# transponder-11_8_0.net
KiCad netlist of a schematic drawn in EAGLE
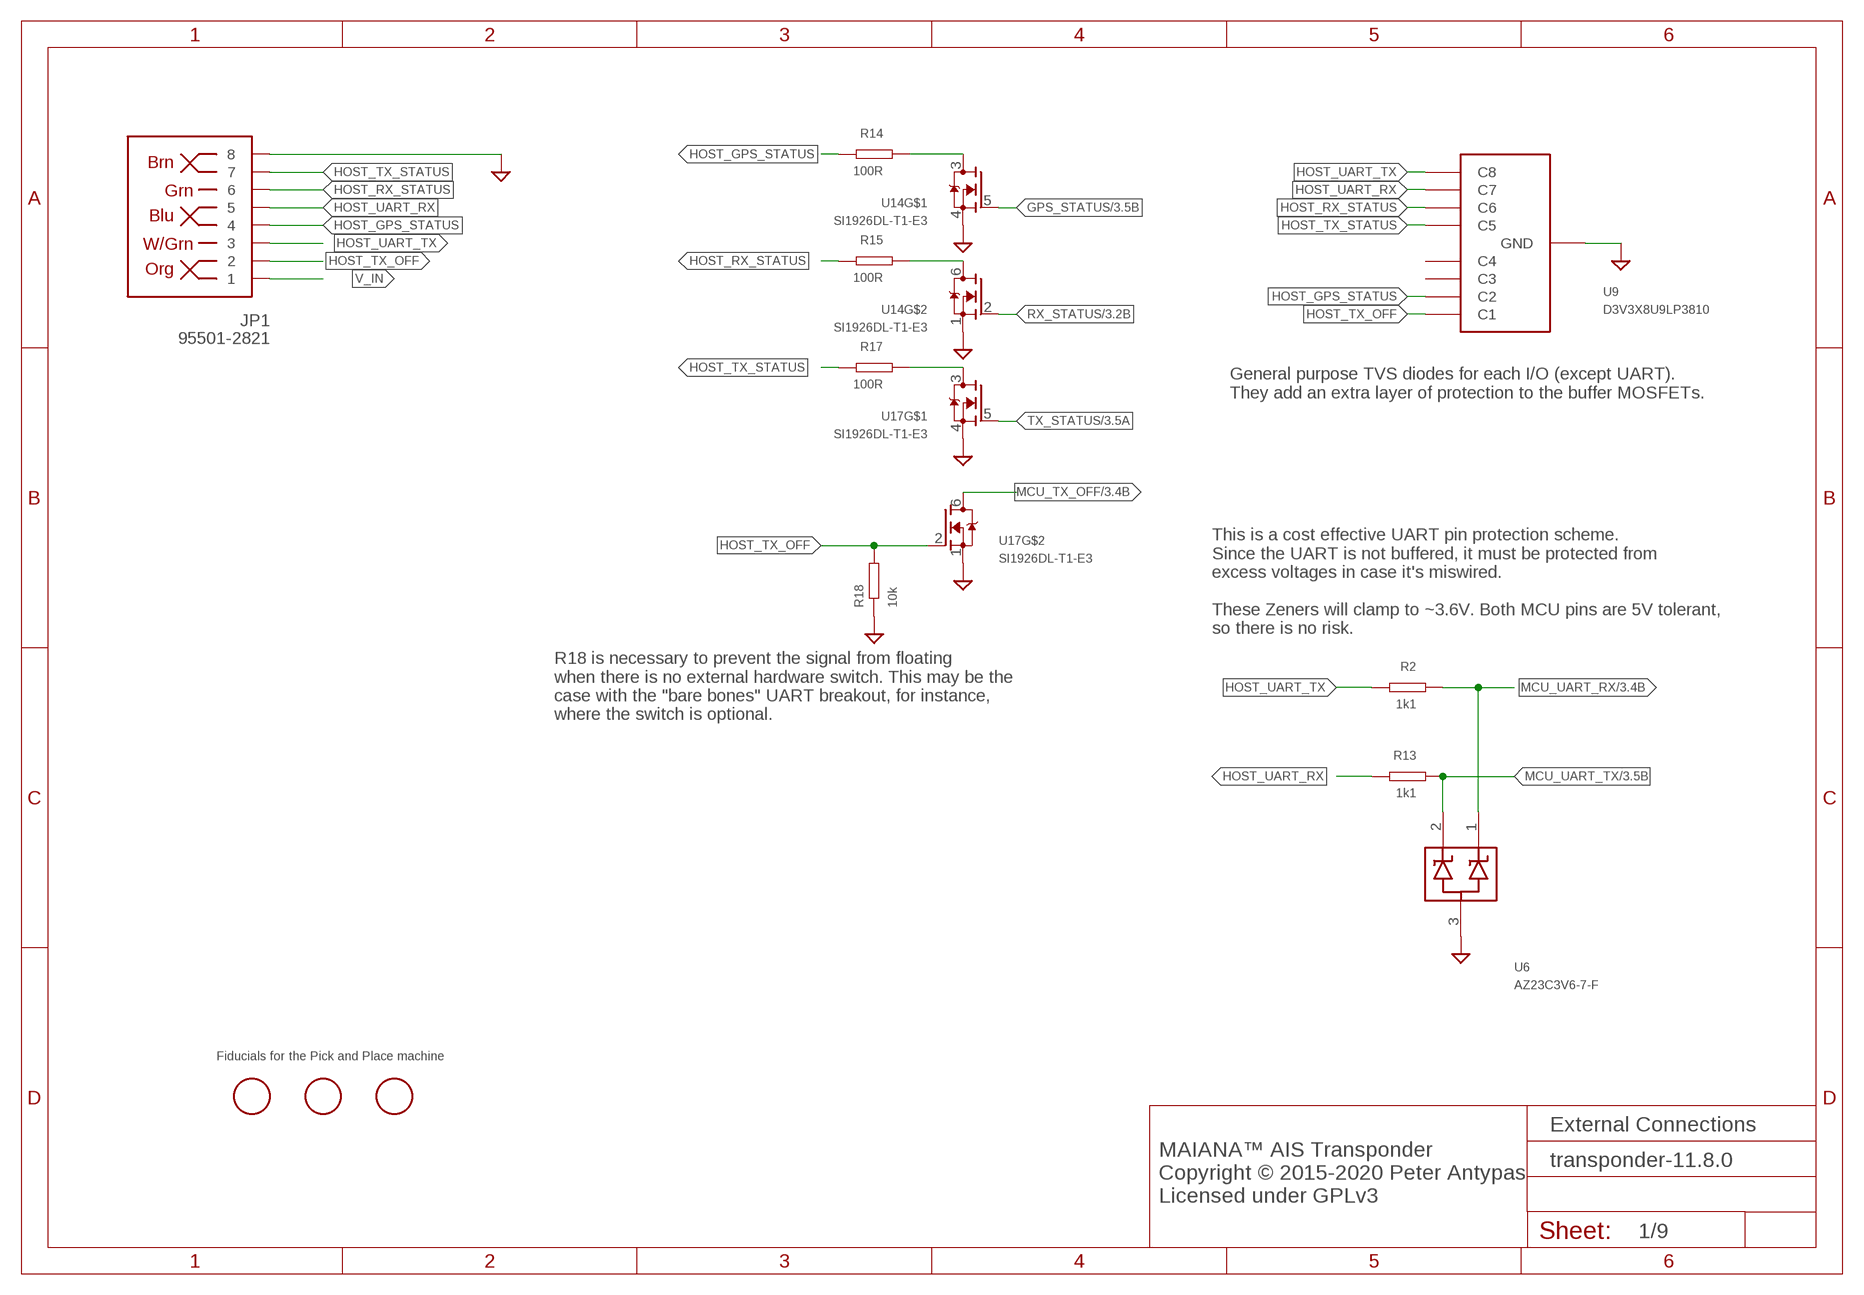
[diagram p0: schematic, sheet 1]
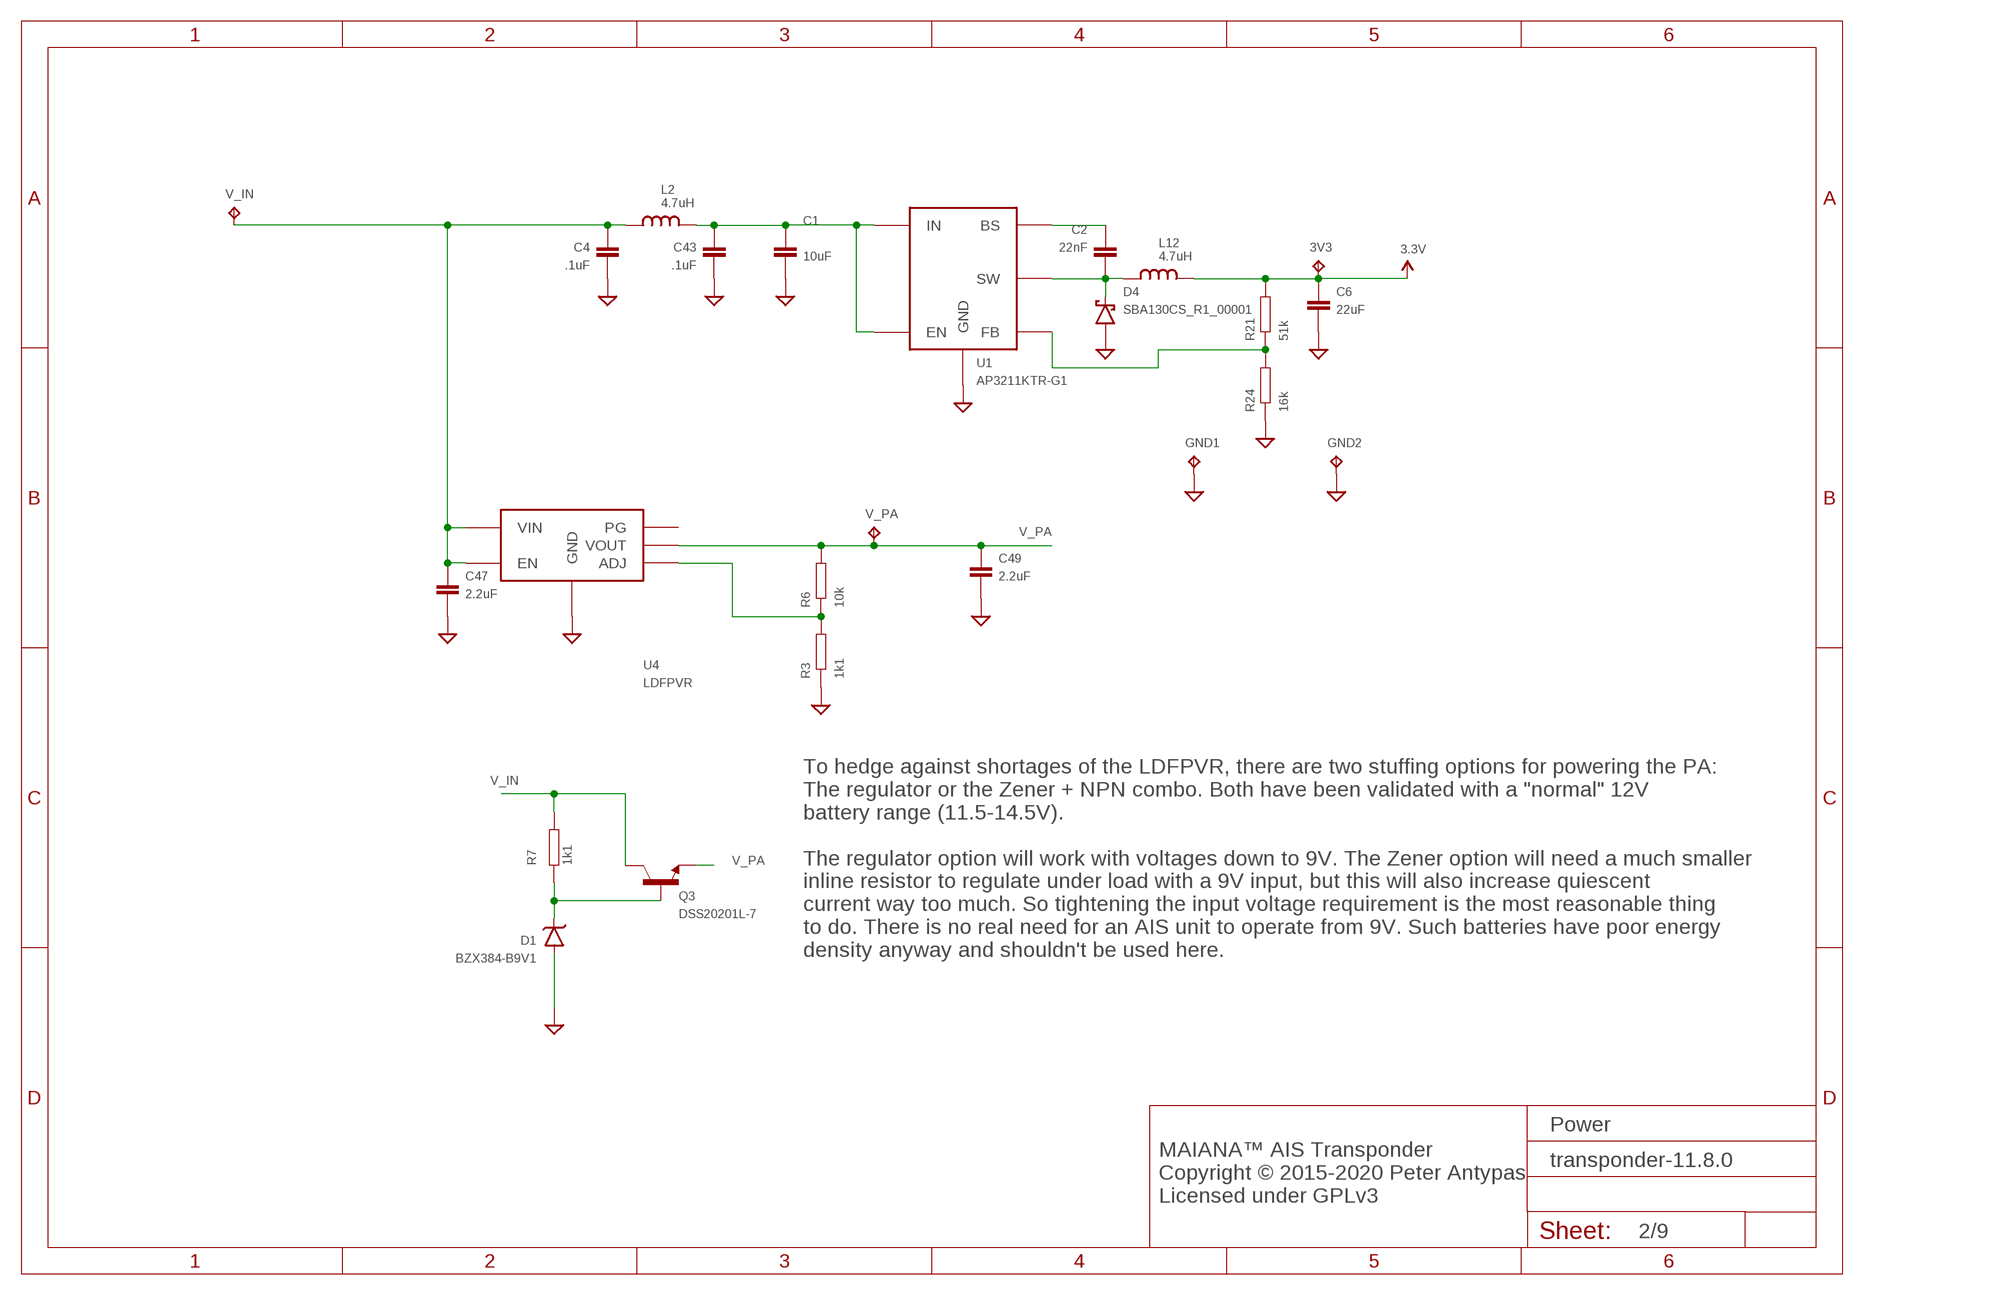
[diagram p1: schematic, sheet 2]
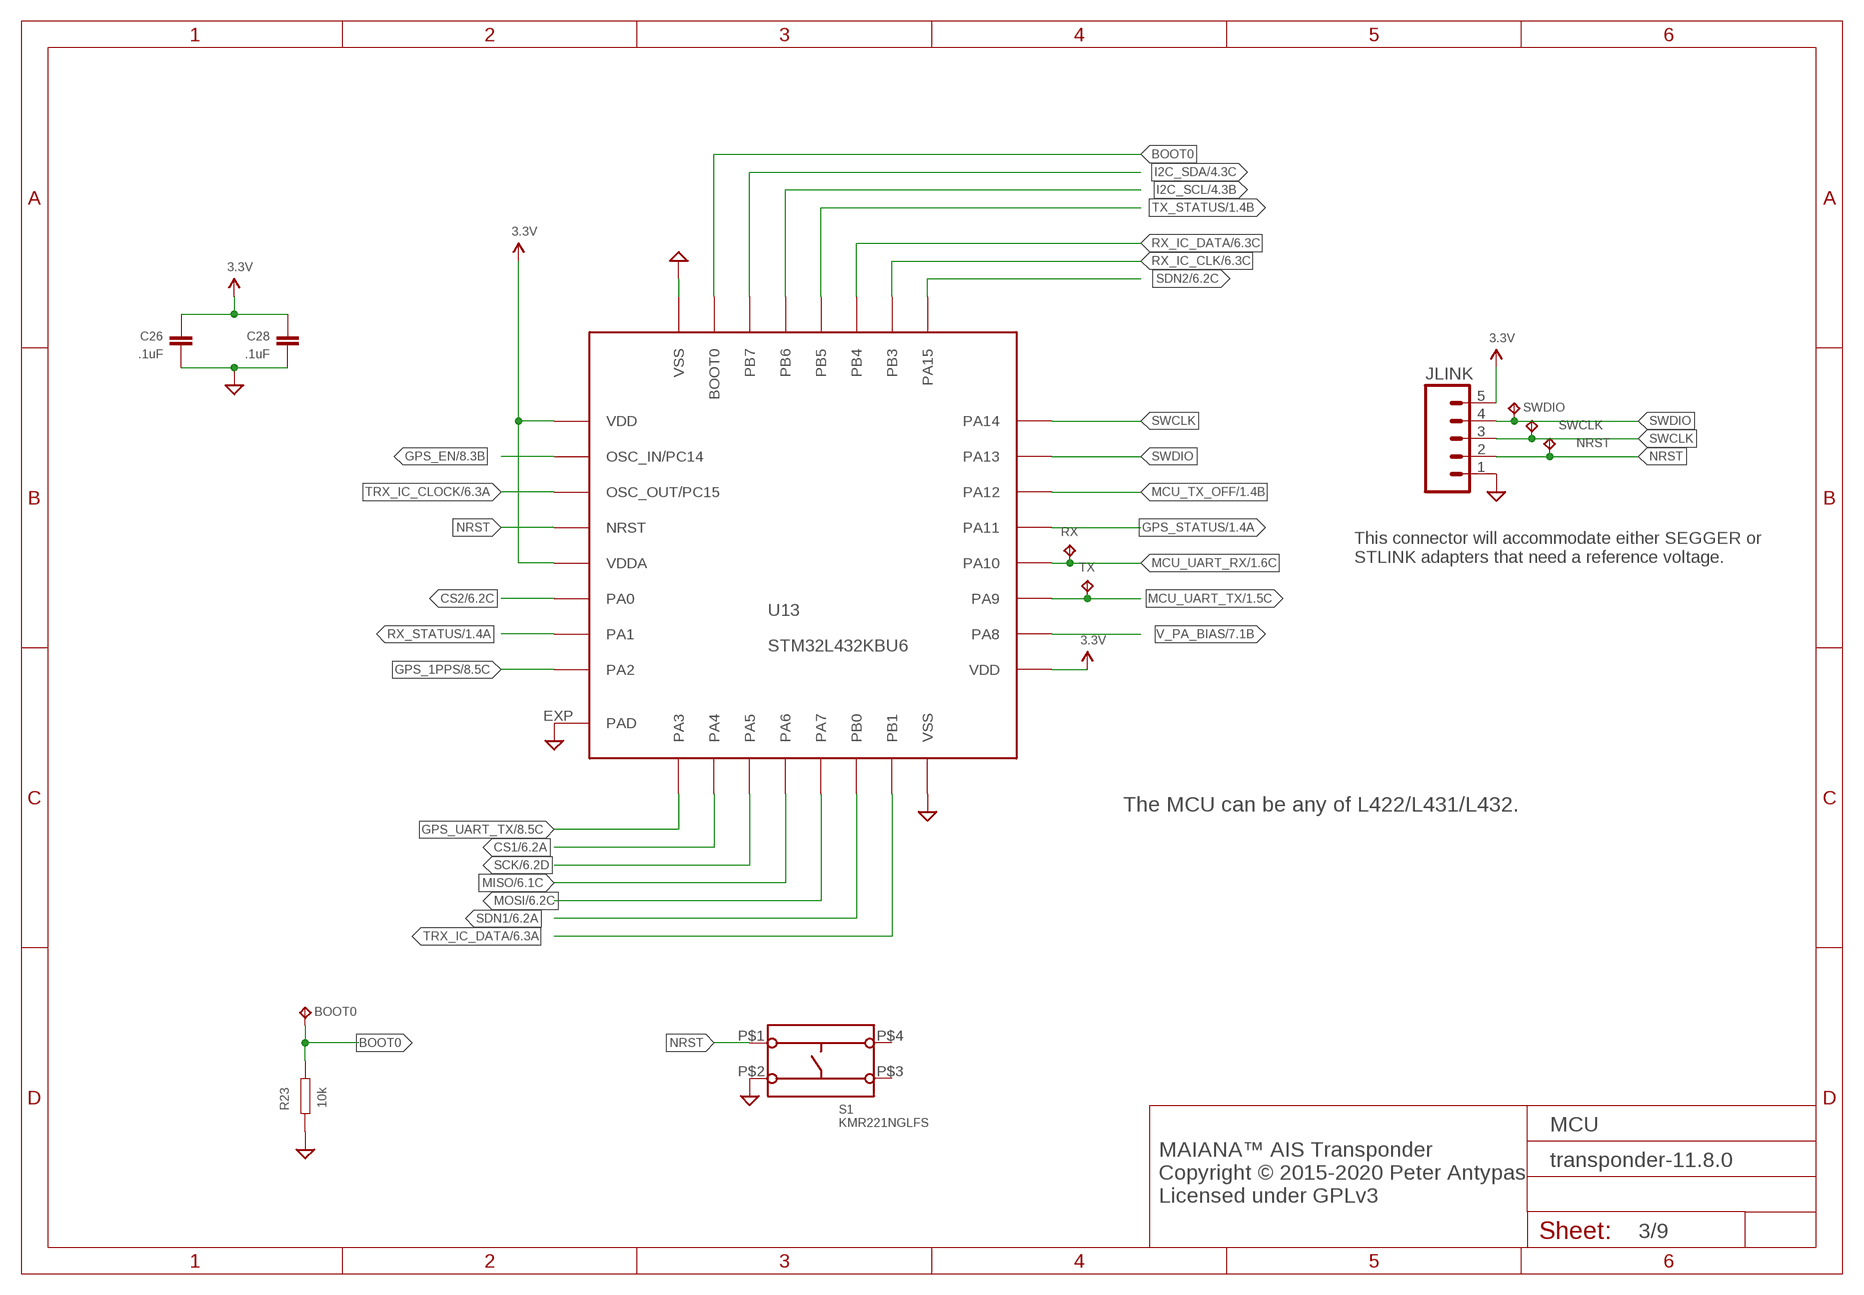
[diagram p2: schematic, sheet 3]
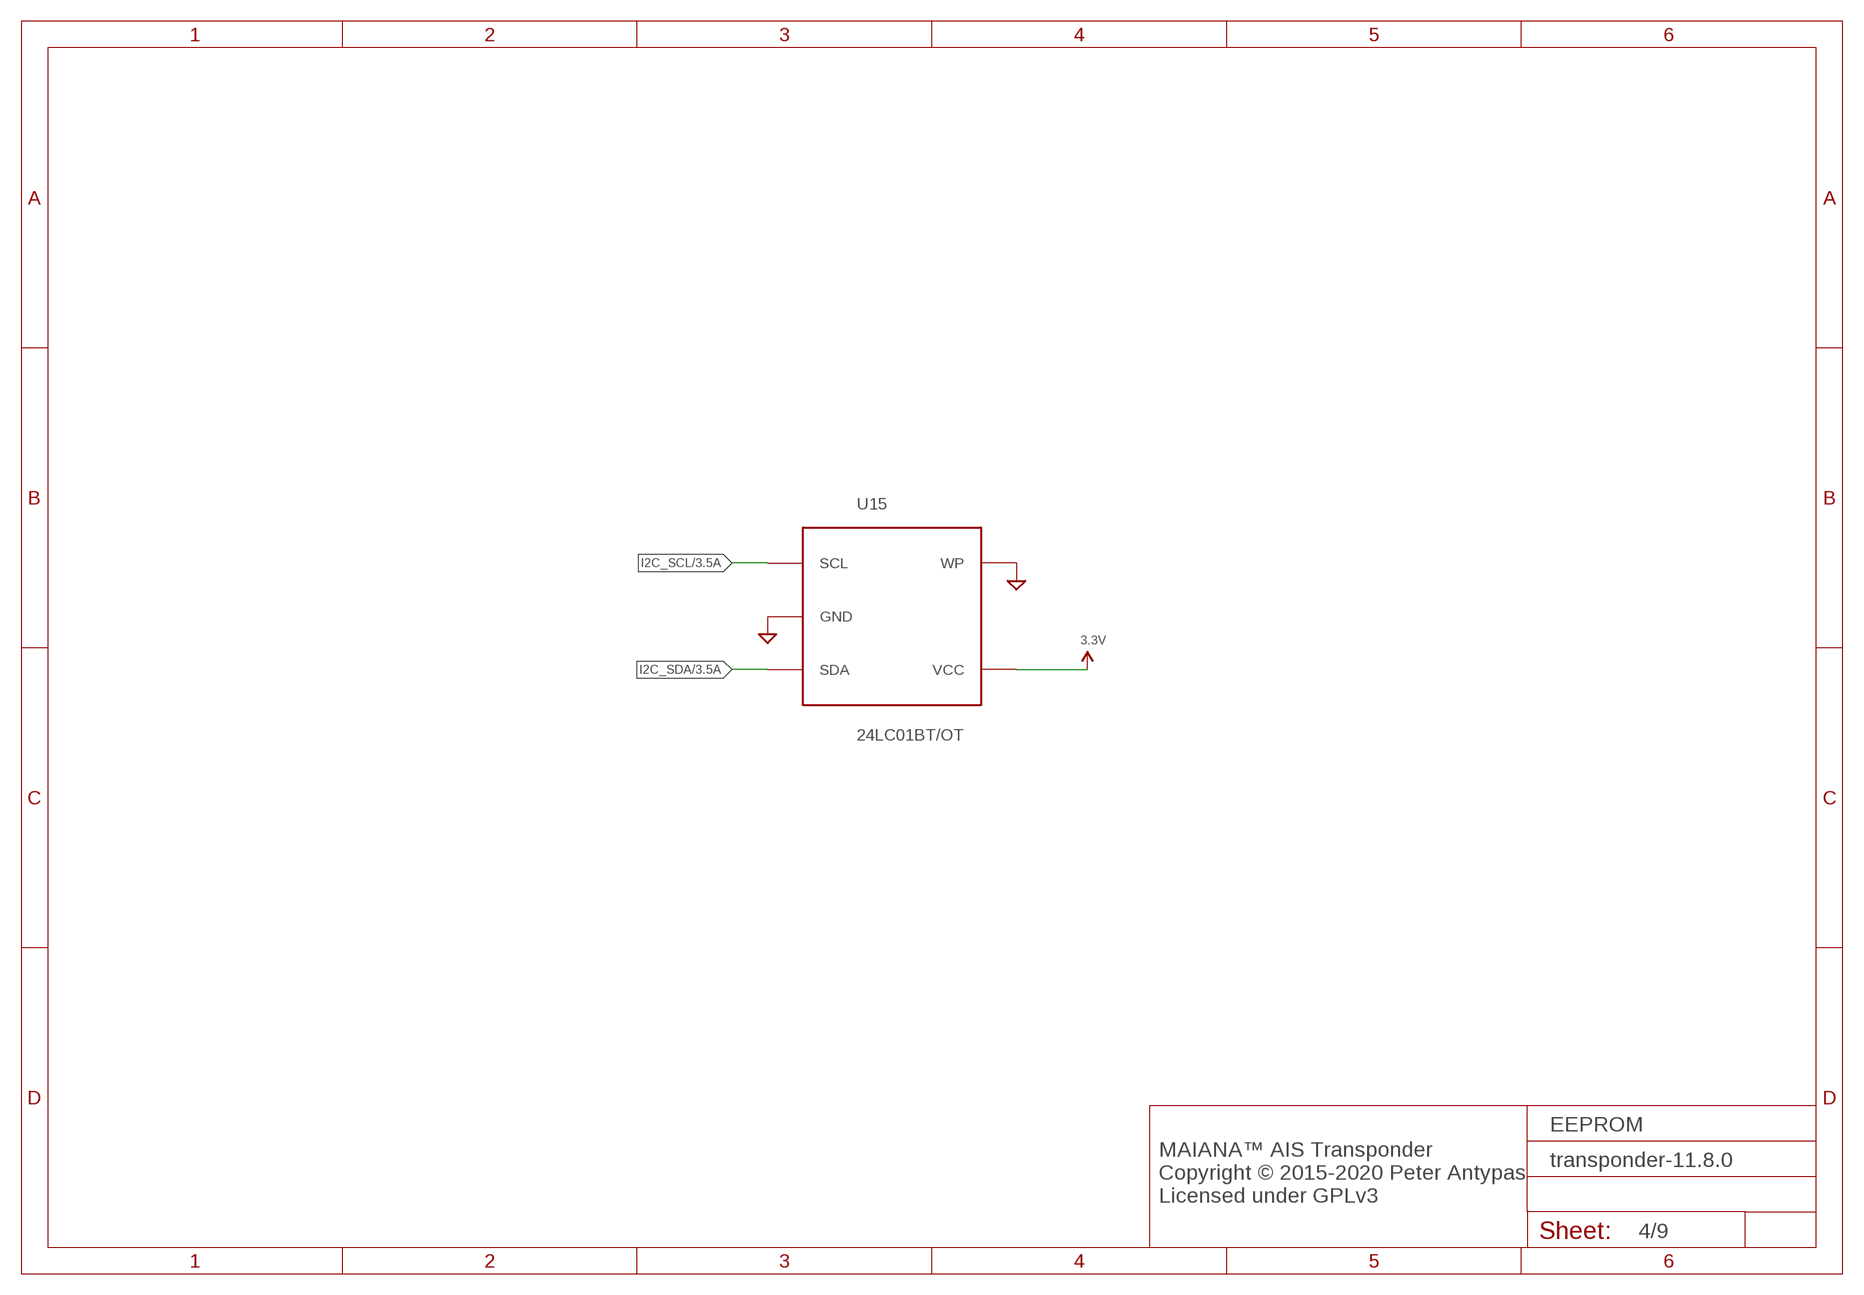
[diagram p3: schematic, sheet 4]
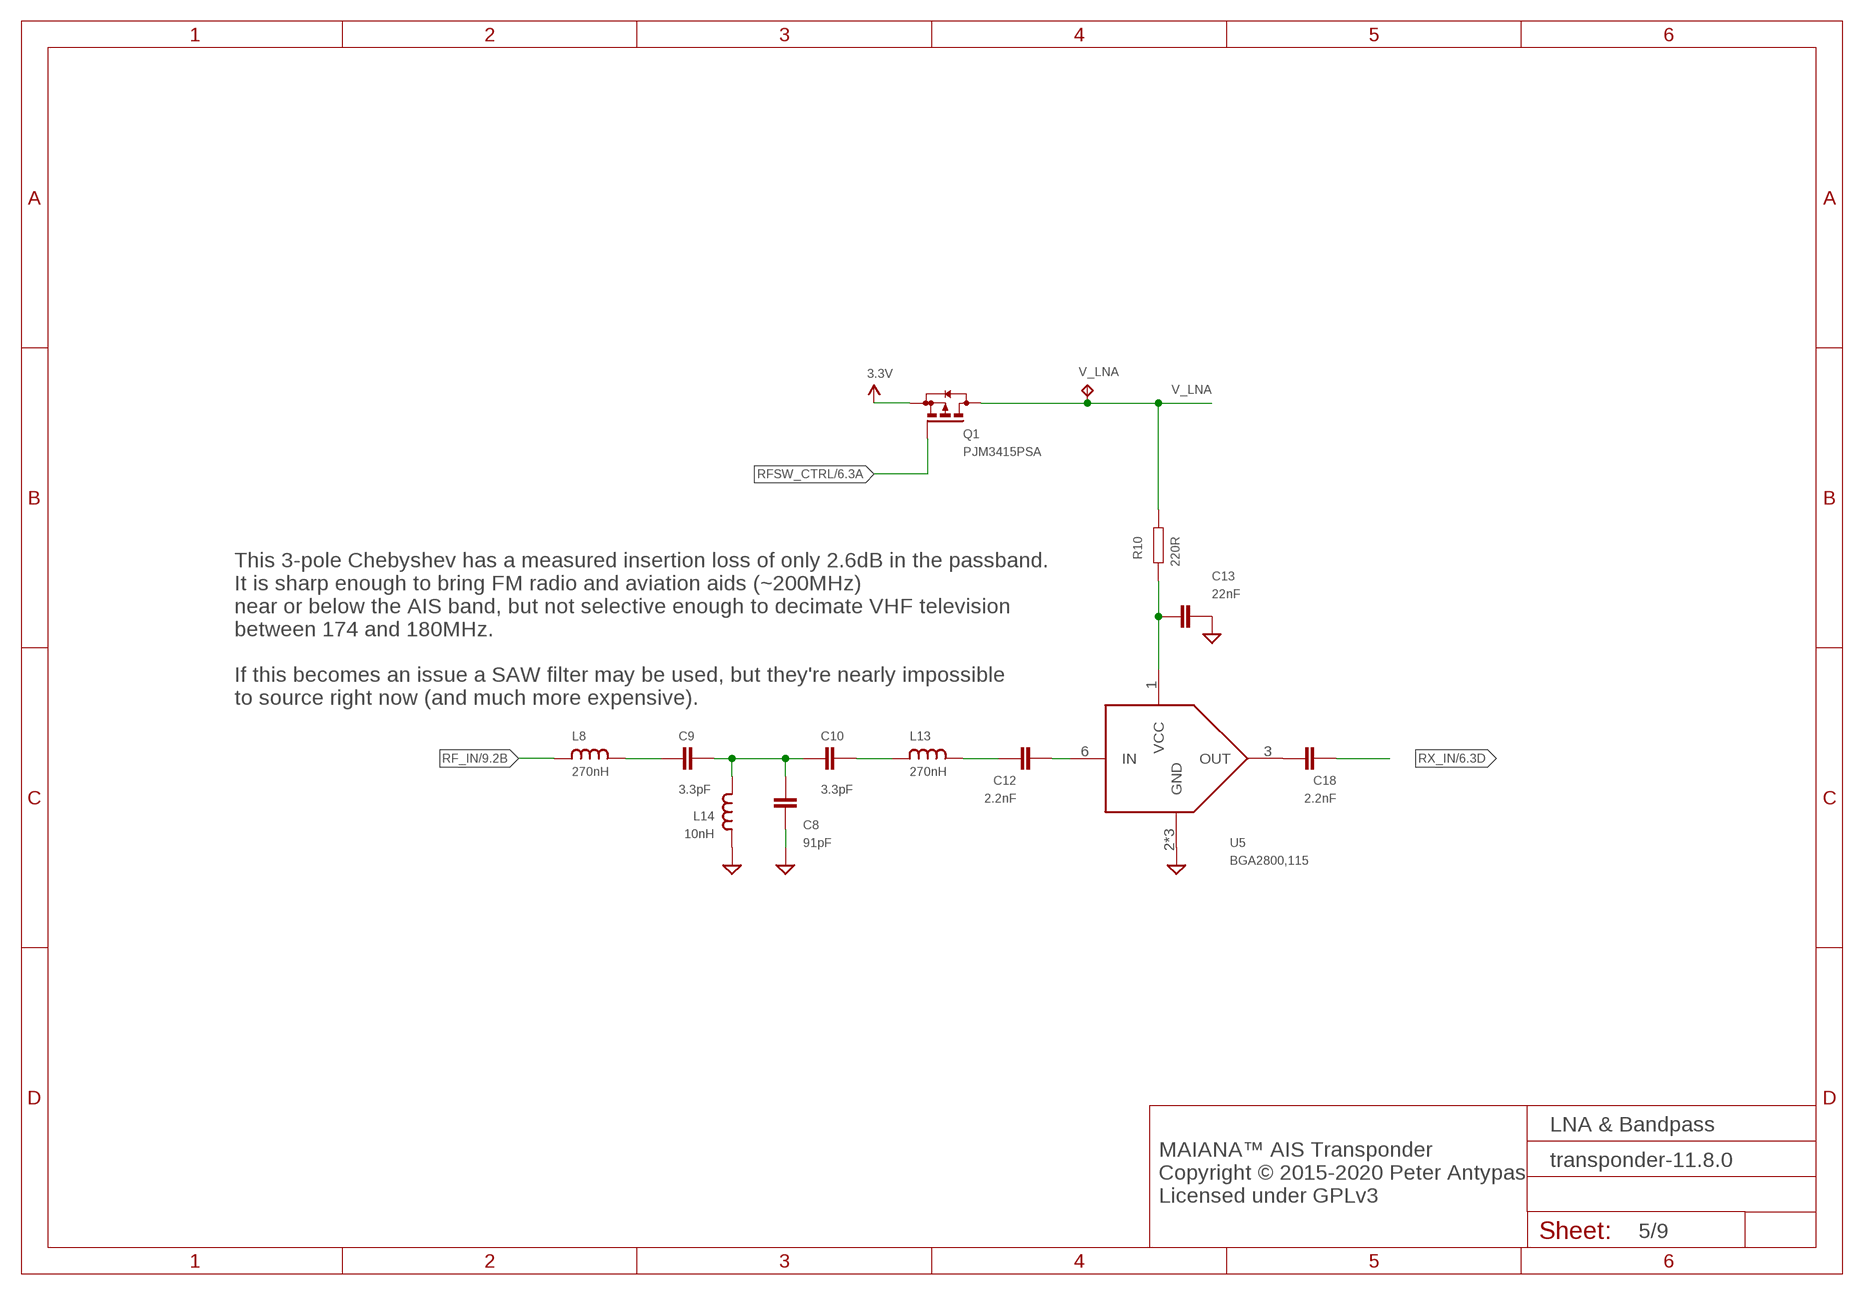
[diagram p4: schematic, sheet 5]
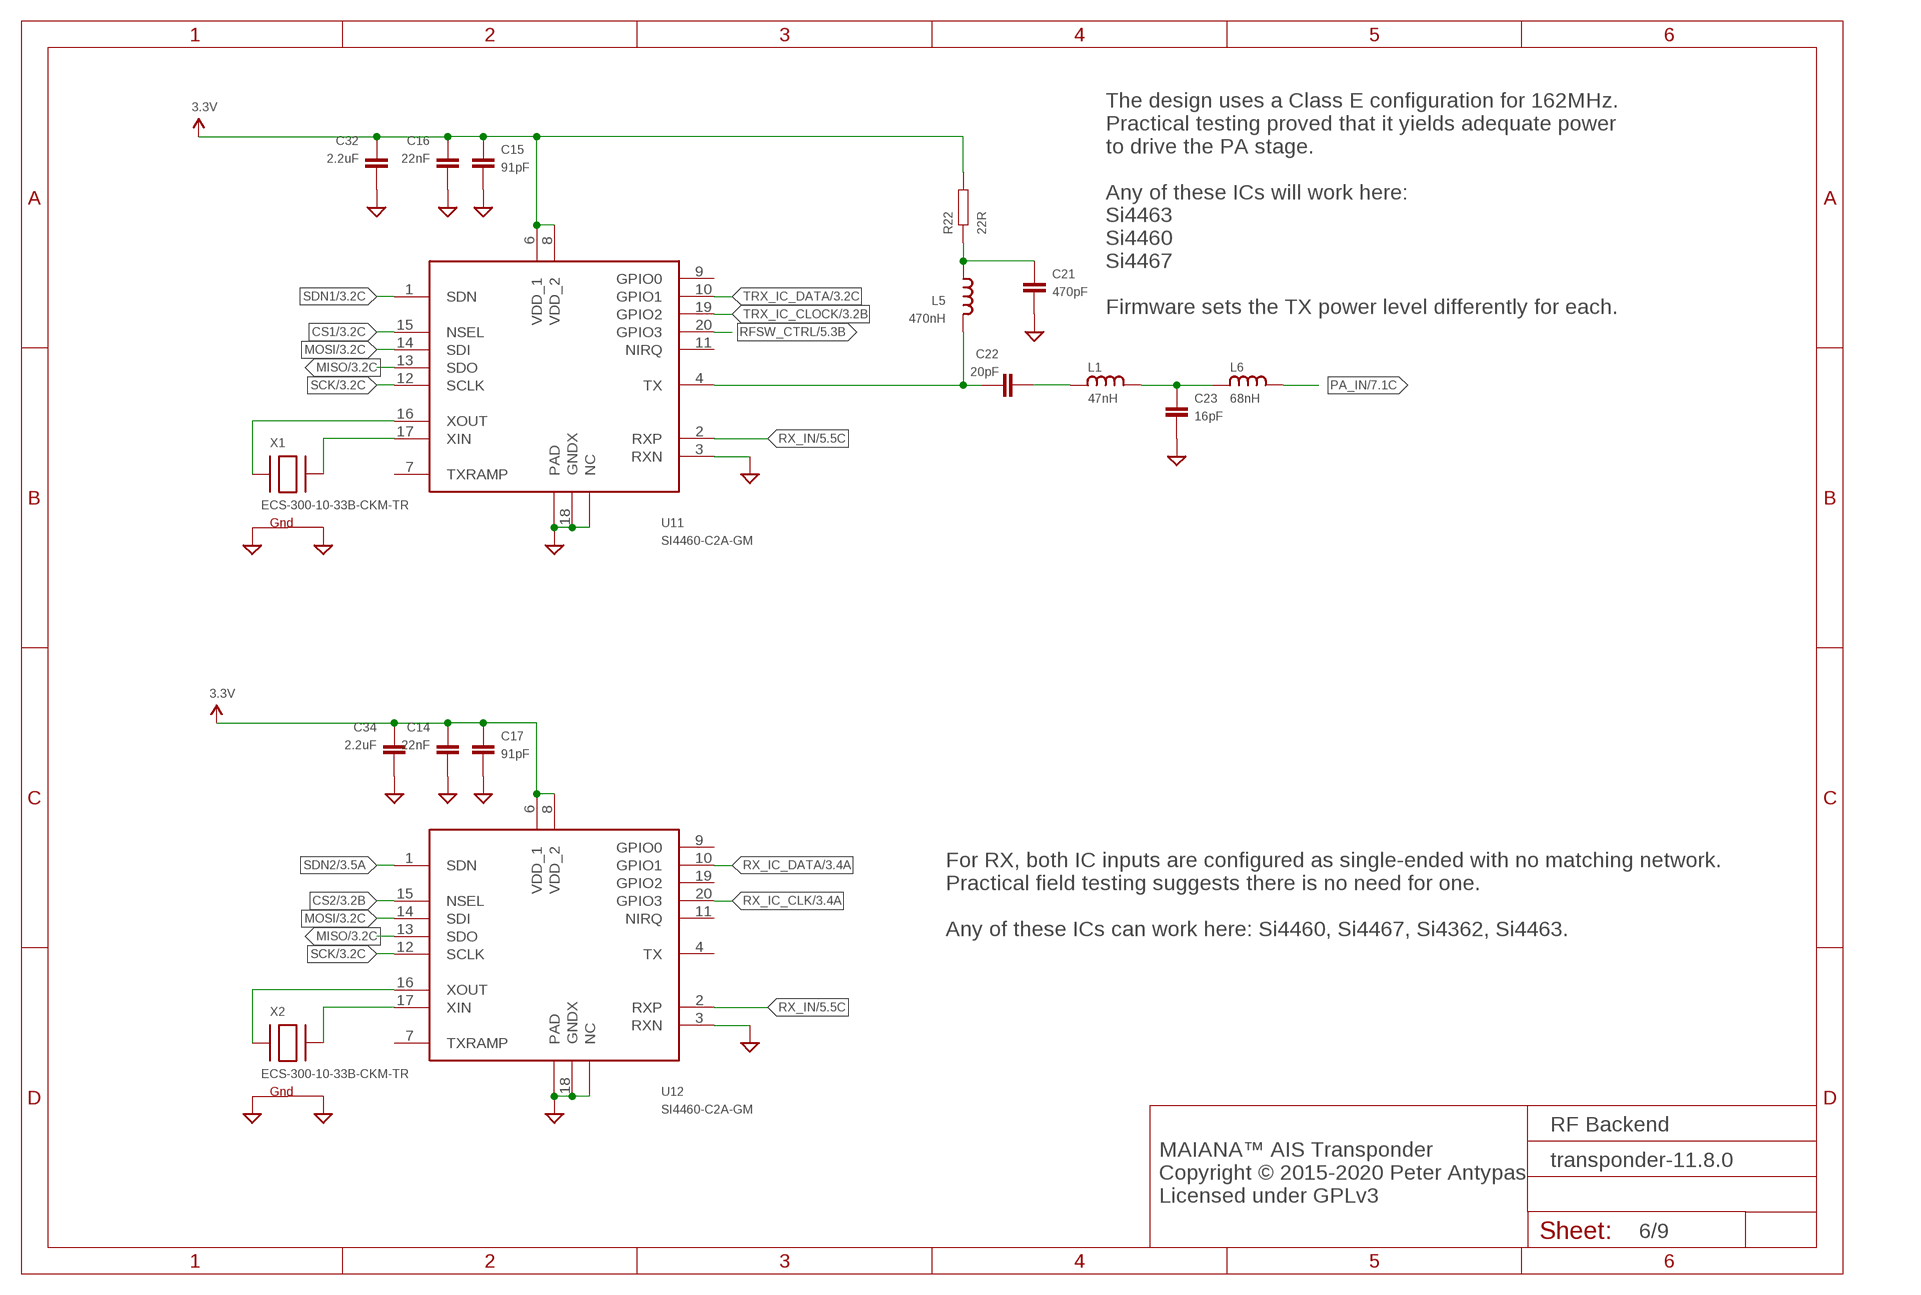
[diagram p5: schematic, sheet 6]
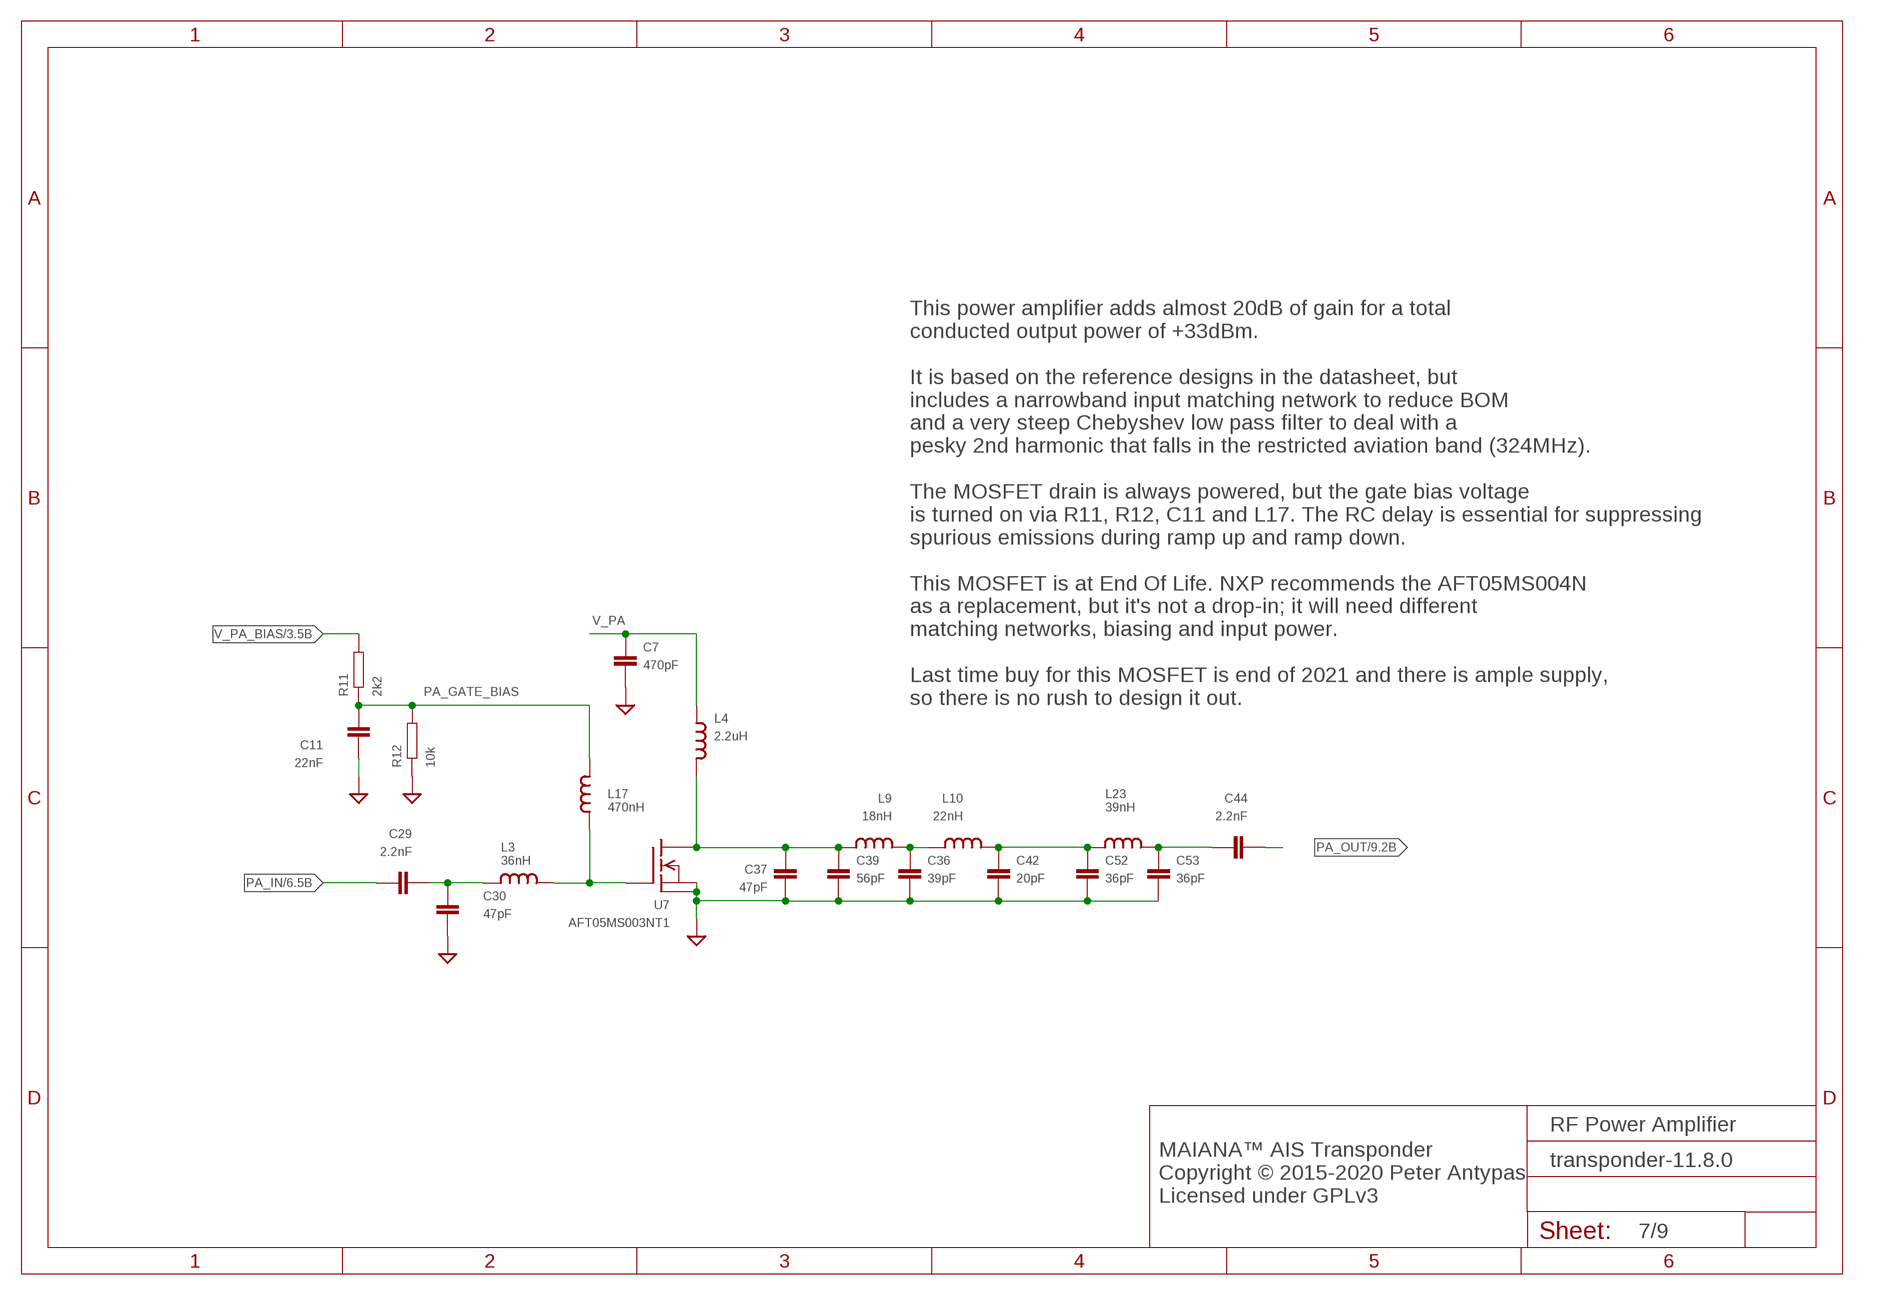
[diagram p6: schematic, sheet 7]
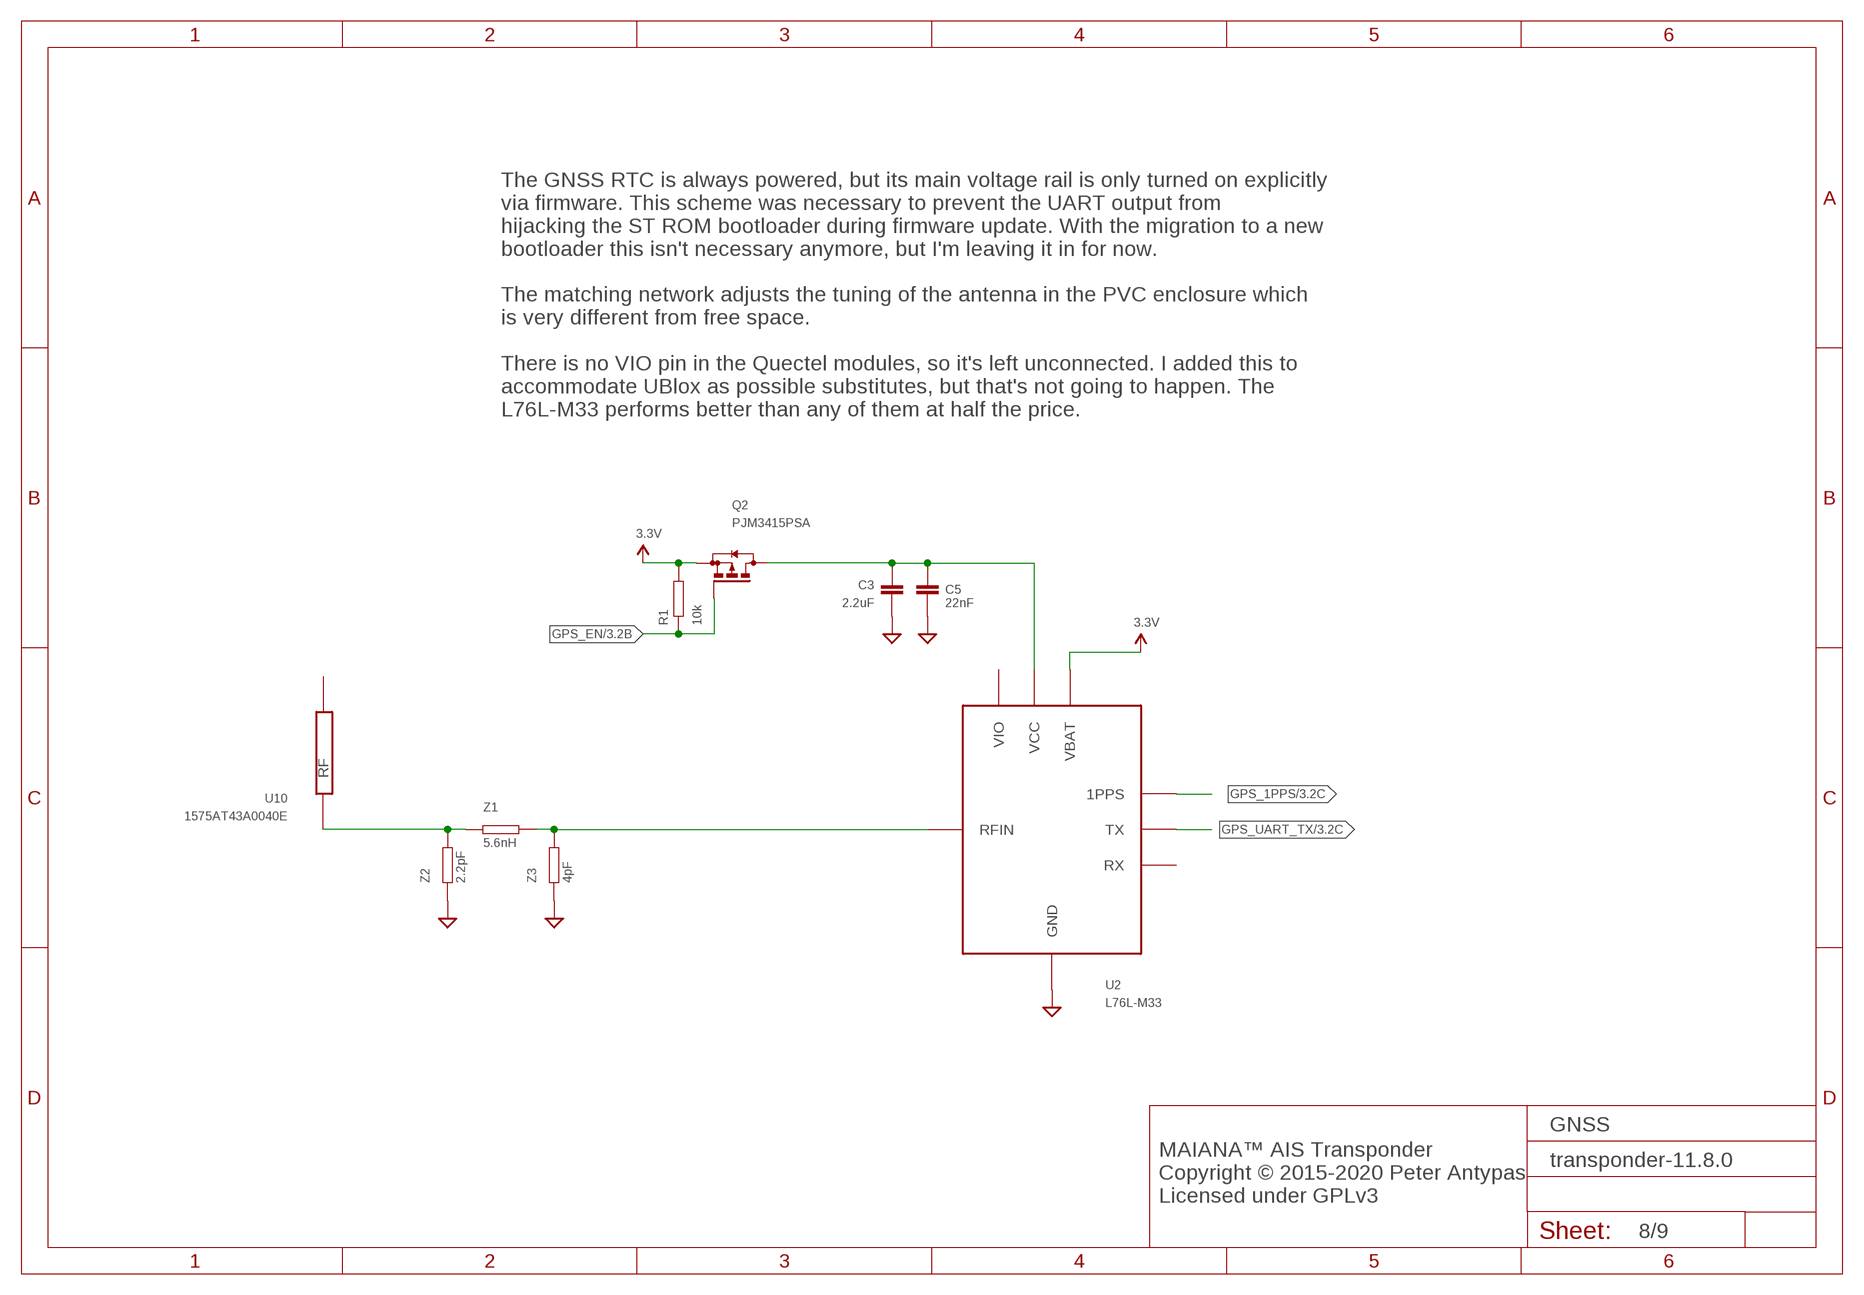
[diagram p7: schematic, sheet 8]
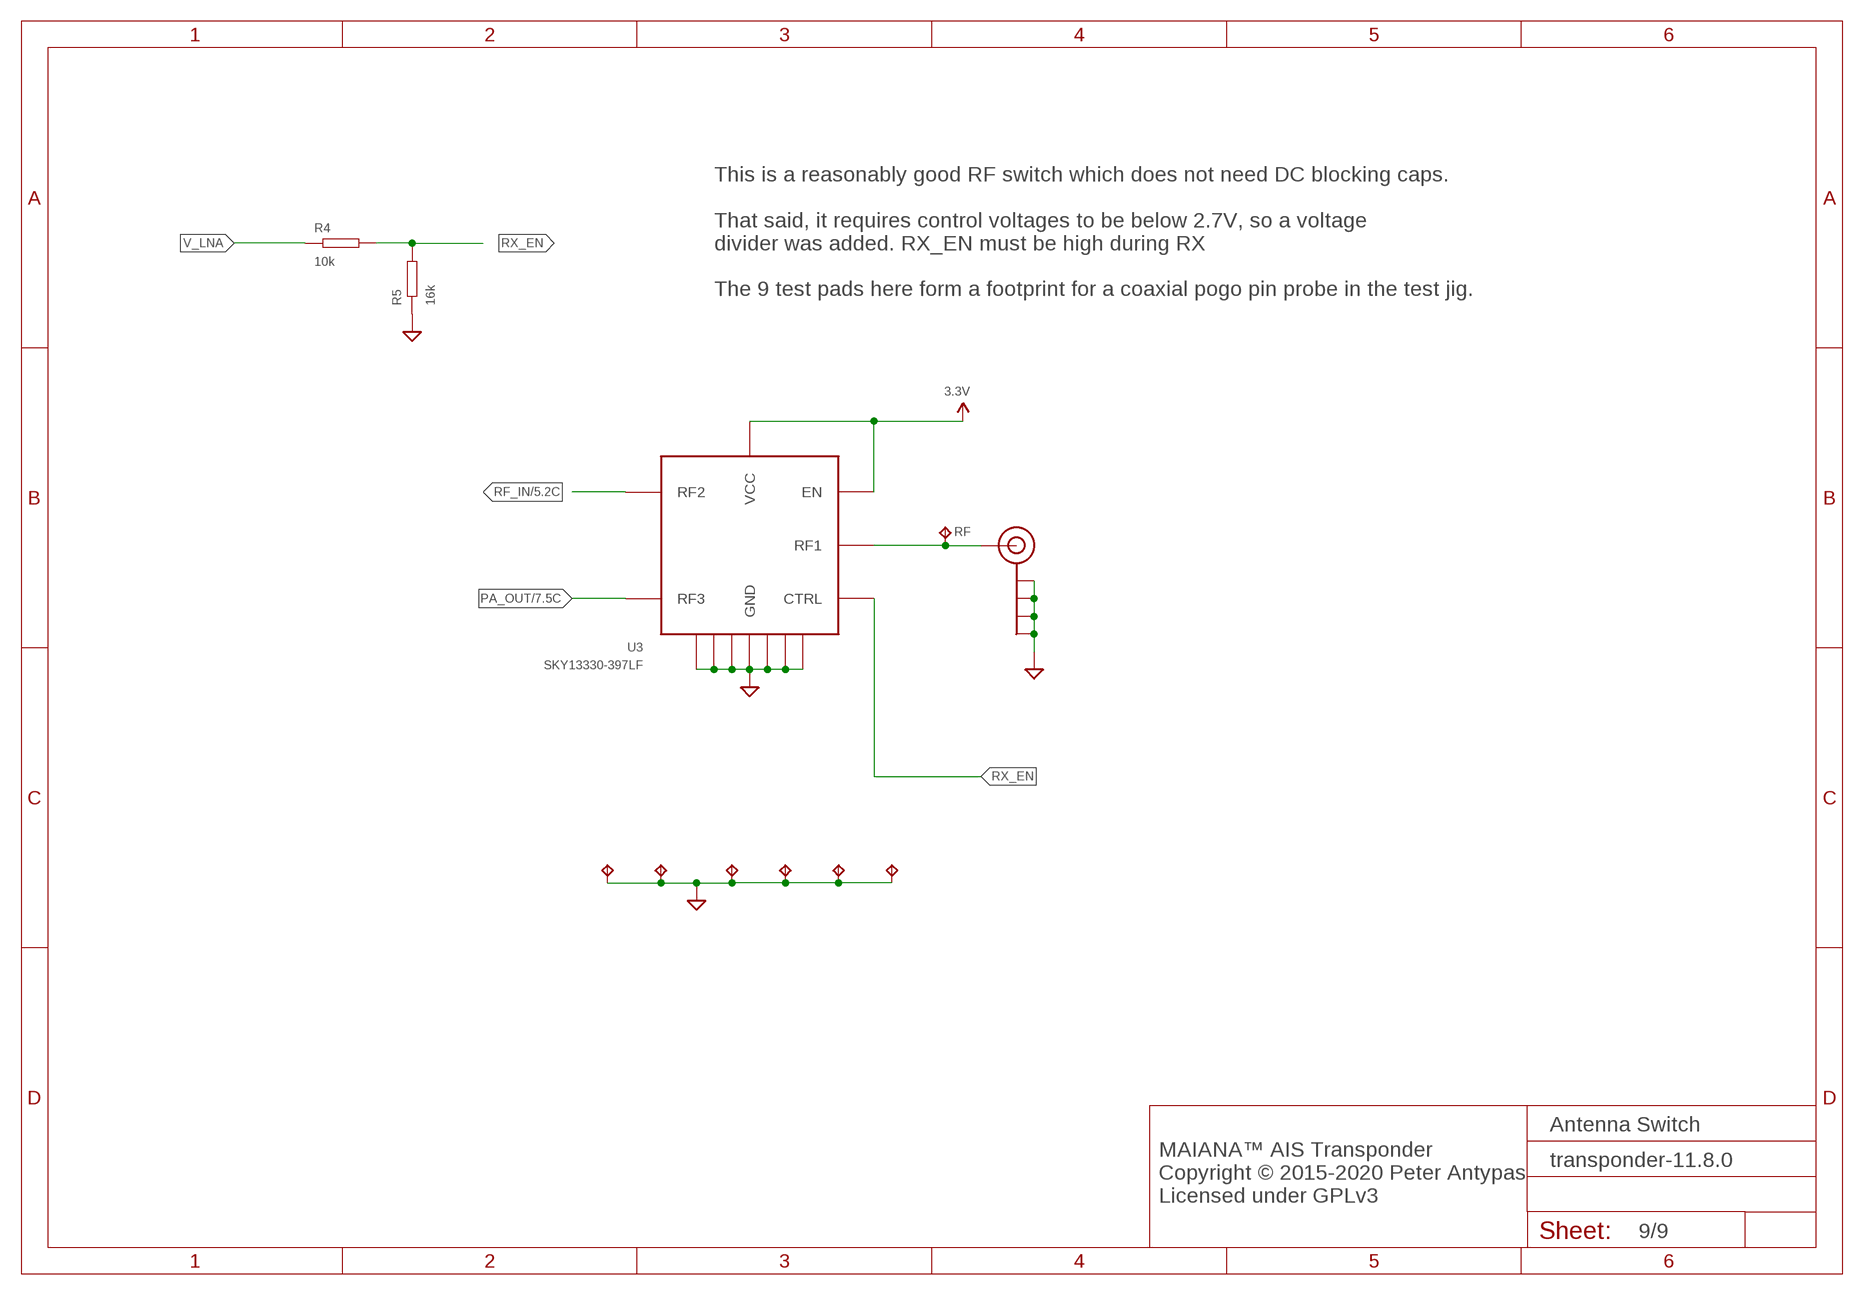
[diagram p8: schematic, sheet 9]

(export (version "E")
  (design (tool "Eeschema 10.0.6"))
  (components
    (comp (ref "U15")
      (value "24LC01BT/OT")
      (footprint "eagle-import:SOT23-5")
      (fields (field (name "PARTNO") "24LC01BT/OT "))
      (libsource (lib "eagle-import") (part "24LC01B"))
    )
    (comp (ref "C3")
      (value "2.2uF")
      (footprint "eagle-import:0603")
      (fields (field (name "PARTNO") "0603X225K160CT"))
      (libsource (lib "eagle-import") (part "CAPACITOR0603"))
    )
    (comp (ref "C5")
      (value "22nF")
      (footprint "eagle-import:0603")
      (fields (field (name "PARTNO") "CL10B223KA8NNNC"))
      (libsource (lib "eagle-import") (part "CAPACITOR0603"))
    )
    (comp (ref "Q2")
      (value "PJM3415PSA")
      (footprint "eagle-import:SOT23")
      (libsource (lib "eagle-import") (part "BSS84"))
    )
    (comp (ref "R1")
      (value "10k")
      (footprint "eagle-import:0603")
      (fields (field (name "PARTNO") "CR0603JA0103G"))
      (libsource (lib "eagle-import") (part "RESISTOR0603"))
    )
    (comp (ref "U2")
      (value "L76L-M33")
      (footprint "eagle-import:GPS_MODULE")
      (fields (field (name "PARTNO") "L76L-M33"))
      (libsource (lib "eagle-import") (part "L70"))
    )
    (comp (ref "U10")
      (value "1575AT43A0040E")
      (footprint "eagle-import:1575AT43A0040E")
      (libsource (lib "eagle-import") (part "1575AT43A0040E"))
    )
    (comp (ref "Z1")
      (value "5.6nH")
      (footprint "eagle-import:0603")
      (fields (field (name "PARTNO") "LQW18AN5N6C00D"))
      (libsource (lib "eagle-import") (part "RESISTOR0603"))
    )
    (comp (ref "Z2")
      (value "2.2pF")
      (footprint "eagle-import:0603")
      (fields (field (name "PARTNO") "0603N2R2B500CT"))
      (libsource (lib "eagle-import") (part "RESISTOR0603"))
    )
    (comp (ref "Z3")
      (value "4pF")
      (footprint "eagle-import:0603")
      (fields (field (name "PARTNO") "RF18N4R0B500CT"))
      (libsource (lib "eagle-import") (part "RESISTOR0603"))
    )
    (comp (ref "C8")
      (value "91pF")
      (footprint "eagle-import:0603")
      (fields (field (name "PARTNO") "CC0603JRNPO9BN910 "))
      (libsource (lib "eagle-import") (part "CAPACITOR0603"))
    )
    (comp (ref "C9")
      (value "3.3pF")
      (footprint "eagle-import:0603")
      (fields (field (name "PARTNO") "0603N3R3B500CT "))
      (libsource (lib "eagle-import") (part "CAPACITOR0603"))
    )
    (comp (ref "C10")
      (value "3.3pF")
      (footprint "eagle-import:0603")
      (fields (field (name "PARTNO") "0603N3R3B500CT "))
      (libsource (lib "eagle-import") (part "CAPACITOR0603"))
    )
    (comp (ref "C12")
      (value "2.2nF")
      (footprint "eagle-import:0603")
      (fields (field (name "PARTNO") "0603N222J500CT"))
      (libsource (lib "eagle-import") (part "CAPACITOR0603"))
    )
    (comp (ref "C13")
      (value "22nF")
      (footprint "eagle-import:0603")
      (fields (field (name "PARTNO") "CL10B223KA8NNNC"))
      (libsource (lib "eagle-import") (part "CAPACITOR0603"))
    )
    (comp (ref "C18")
      (value "2.2nF")
      (footprint "eagle-import:0603")
      (fields (field (name "PARTNO") "0603N222J500CT"))
      (libsource (lib "eagle-import") (part "CAPACITOR0603"))
    )
    (comp (ref "L8")
      (value "270nH")
      (footprint "eagle-import:0603")
      (fields (field (name "PARTNO") "LQW18ANR27G00D "))
      (libsource (lib "eagle-import") (part "INDUCTOR0603"))
    )
    (comp (ref "L13")
      (value "270nH")
      (footprint "eagle-import:0603")
      (fields (field (name "PARTNO") "LQW18ANR27G00D "))
      (libsource (lib "eagle-import") (part "INDUCTOR0603"))
    )
    (comp (ref "L14")
      (value "10nH")
      (footprint "eagle-import:0603")
      (fields (field (name "PARTNO") "LQW18AN10NG00D"))
      (libsource (lib "eagle-import") (part "INDUCTOR0603"))
    )
    (comp (ref "Q1")
      (value "PJM3415PSA")
      (footprint "eagle-import:SOT23")
      (libsource (lib "eagle-import") (part "BSS84"))
    )
    (comp (ref "R10")
      (value "220R")
      (footprint "eagle-import:0603")
      (fields (field (name "PARTNO") "CR0603FA2200G "))
      (libsource (lib "eagle-import") (part "RESISTOR0603"))
    )
    (comp (ref "U5")
      (value "BGA2800,115")
      (footprint "eagle-import:SOT363")
      (libsource (lib "eagle-import") (part "BGA2870"))
    )
    (comp (ref "V_LNA")
      (value "TPTP12R")
      (footprint "eagle-import:TP12R")
      (libsource (lib "eagle-import") (part "TPTP12R"))
    )
    (comp (ref "J$1")
      (value "SMA_EDGE")
      (footprint "eagle-import:SMA-EDGE")
      (libsource (lib "eagle-import") (part "SMA_EDGE"))
    )
    (comp (ref "R4")
      (value "10k")
      (footprint "eagle-import:0603")
      (fields (field (name "PARTNO") "CR0603JA0103G"))
      (libsource (lib "eagle-import") (part "RESISTOR0603"))
    )
    (comp (ref "R5")
      (value "16k")
      (footprint "eagle-import:0603")
      (fields (field (name "PARTNO") "RC0603FR-0716KL"))
      (libsource (lib "eagle-import") (part "RESISTOR0603"))
    )
    (comp (ref "RF")
      (value "TPTP10R")
      (footprint "eagle-import:TP10R")
      (libsource (lib "eagle-import") (part "TPTP10R"))
    )
    (comp (ref "SWDIO1")
      (value "TPTP12R")
      (footprint "eagle-import:TP12R")
      (libsource (lib "eagle-import") (part "TPTP12R"))
    )
    (comp (ref "SWDIO2")
      (value "TPTP12R")
      (footprint "eagle-import:TP12R")
      (libsource (lib "eagle-import") (part "TPTP12R"))
    )
    (comp (ref "SWDIO3")
      (value "TPTP12R")
      (footprint "eagle-import:TP12R")
      (libsource (lib "eagle-import") (part "TPTP12R"))
    )
    (comp (ref "SWDIO4")
      (value "TPTP12R")
      (footprint "eagle-import:TP12R")
      (libsource (lib "eagle-import") (part "TPTP12R"))
    )
    (comp (ref "SWDIO5")
      (value "TPTP12R")
      (footprint "eagle-import:TP12R")
      (libsource (lib "eagle-import") (part "TPTP12R"))
    )
    (comp (ref "SWDIO6")
      (value "TPTP12R")
      (footprint "eagle-import:TP12R")
      (libsource (lib "eagle-import") (part "TPTP12R"))
    )
    (comp (ref "U3")
      (value "SKY13330-397LF")
      (footprint "eagle-import:QFN12")
      (libsource (lib "eagle-import") (part "SKYWORKS-13330397LF"))
    )
    (comp (ref "C14")
      (value "22nF")
      (footprint "eagle-import:0603")
      (fields (field (name "PARTNO") "CL10B223KA8NNNC"))
      (libsource (lib "eagle-import") (part "CAPACITOR0603"))
    )
    (comp (ref "C15")
      (value "91pF")
      (footprint "eagle-import:0603")
      (fields (field (name "PARTNO") "CC0603JRNPO9BN910 "))
      (libsource (lib "eagle-import") (part "CAPACITOR0603"))
    )
    (comp (ref "C16")
      (value "22nF")
      (footprint "eagle-import:0603")
      (fields (field (name "PARTNO") "CL10B223KA8NNNC"))
      (libsource (lib "eagle-import") (part "CAPACITOR0603"))
    )
    (comp (ref "C17")
      (value "91pF")
      (footprint "eagle-import:0603")
      (fields (field (name "PARTNO") "CC0603JRNPO9BN910 "))
      (libsource (lib "eagle-import") (part "CAPACITOR0603"))
    )
    (comp (ref "C21")
      (value "470pF")
      (footprint "eagle-import:0603")
      (fields (field (name "PARTNO") "0603B471K500CT "))
      (libsource (lib "eagle-import") (part "CAPACITOR0603"))
    )
    (comp (ref "C22")
      (value "20pF")
      (footprint "eagle-import:0603")
      (fields (field (name "PARTNO") "CL10C200JB8NNNC"))
      (libsource (lib "eagle-import") (part "CAPACITOR0603"))
    )
    (comp (ref "C23")
      (value "16pF")
      (footprint "eagle-import:0603")
      (fields (field (name "PARTNO") "0603N160G500CT"))
      (libsource (lib "eagle-import") (part "CAPACITOR0603"))
    )
    (comp (ref "C32")
      (value "2.2uF")
      (footprint "eagle-import:0603")
      (fields (field (name "PARTNO") "0603X225K160CT"))
      (libsource (lib "eagle-import") (part "CAPACITOR0603"))
    )
    (comp (ref "C34")
      (value "2.2uF")
      (footprint "eagle-import:0603")
      (fields (field (name "PARTNO") "0603X225K160CT"))
      (libsource (lib "eagle-import") (part "CAPACITOR0603"))
    )
    (comp (ref "L1")
      (value "47nH")
      (footprint "eagle-import:0603")
      (fields (field (name "PARTNO") "LQW18AN47NG00D"))
      (libsource (lib "eagle-import") (part "INDUCTOR0603"))
    )
    (comp (ref "L5")
      (value "470nH")
      (footprint "eagle-import:0603")
      (fields (field (name "PARTNO") "HBLS1608-R47J "))
      (libsource (lib "eagle-import") (part "INDUCTOR0603"))
    )
    (comp (ref "L6")
      (value "68nH")
      (footprint "eagle-import:0603")
      (fields (field (name "PARTNO") "LQW18AN68NG00D "))
      (libsource (lib "eagle-import") (part "INDUCTOR0603"))
    )
    (comp (ref "R22")
      (value "22R")
      (footprint "eagle-import:0603")
      (fields (field (name "PARTNO") "RC0603JR-0722RL "))
      (libsource (lib "eagle-import") (part "RESISTOR0603"))
    )
    (comp (ref "U11")
      (value "SI4460-C2A-GM")
      (footprint "eagle-import:QFN20")
      (libsource (lib "eagle-import") (part "SI4463"))
    )
    (comp (ref "U12")
      (value "SI4460-C2A-GM")
      (footprint "eagle-import:QFN20")
      (libsource (lib "eagle-import") (part "SI4463"))
    )
    (comp (ref "X1")
      (value "ECS-300-10-33B-CKM-TR")
      (footprint "eagle-import:NX3225")
      (libsource (lib "eagle-import") (part "XTAL-4-3225"))
    )
    (comp (ref "X2")
      (value "ECS-300-10-33B-CKM-TR")
      (footprint "eagle-import:NX3225")
      (libsource (lib "eagle-import") (part "XTAL-4-3225"))
    )
    (comp (ref "3V3")
      (value "TPTP12R")
      (footprint "eagle-import:TP12R")
      (libsource (lib "eagle-import") (part "TPTP12R"))
    )
    (comp (ref "C1")
      (value "10uF")
      (footprint "eagle-import:0805")
      (fields (field (name "PARTNO") "EMK212ABJ106KG-T"))
      (libsource (lib "eagle-import") (part "CAPACITOR0805"))
    )
    (comp (ref "C2")
      (value "22nF")
      (footprint "eagle-import:0603")
      (fields (field (name "PARTNO") "CL10B223KA8NNNC"))
      (libsource (lib "eagle-import") (part "CAPACITOR0603"))
    )
    (comp (ref "C4")
      (value ".1uF")
      (footprint "eagle-import:0603")
      (fields (field (name "PARTNO") "0603B104K250CT"))
      (libsource (lib "eagle-import") (part "CAPACITOR0603"))
    )
    (comp (ref "C6")
      (value "22uF")
      (footprint "eagle-import:0805")
      (fields (field (name "PARTNO") "CL21A226KOQNNNE "))
      (libsource (lib "eagle-import") (part "CAPACITOR0805"))
    )
    (comp (ref "C43")
      (value ".1uF")
      (footprint "eagle-import:0603")
      (fields (field (name "PARTNO") "0603B104K250CT"))
      (libsource (lib "eagle-import") (part "CAPACITOR0603"))
    )
    (comp (ref "C47")
      (value "2.2uF")
      (footprint "eagle-import:0603")
      (fields (field (name "PARTNO") "0603X225K160CT "))
      (libsource (lib "eagle-import") (part "CAPACITOR0603"))
    )
    (comp (ref "C49")
      (value "2.2uF")
      (footprint "eagle-import:0603")
      (fields (field (name "PARTNO") "0603X225K160CT"))
      (libsource (lib "eagle-import") (part "CAPACITOR0603"))
    )
    (comp (ref "D1")
      (value "BZX384-B9V1")
      (footprint "eagle-import:SOD323")
      (libsource (lib "eagle-import") (part "DIODE-ZENERSOD323"))
    )
    (comp (ref "D4")
      (value "SBA130CS_R1_00001")
      (footprint "eagle-import:SOD323")
      (libsource (lib "eagle-import") (part "DIODE-SCHOTTKYSOD323"))
    )
    (comp (ref "GND1")
      (value "TPTP12R")
      (footprint "eagle-import:TP12R")
      (libsource (lib "eagle-import") (part "TPTP12R"))
    )
    (comp (ref "GND2")
      (value "TPTP12R")
      (footprint "eagle-import:TP12R")
      (libsource (lib "eagle-import") (part "TPTP12R"))
    )
    (comp (ref "L2")
      (value "4.7uH")
      (footprint "eagle-import:0805")
      (fields (field (name "PARTNO") "CMP201209UD4R7MT "))
      (libsource (lib "eagle-import") (part "INDUCTOR0805"))
    )
    (comp (ref "L12")
      (value "4.7uH")
      (footprint "eagle-import:0805")
      (fields (field (name "PARTNO") "CMP201209UD4R7MT "))
      (libsource (lib "eagle-import") (part "INDUCTOR0805"))
    )
    (comp (ref "Q3")
      (value "DSS20201L-7")
      (footprint "eagle-import:SOT23-3")
      (libsource (lib "eagle-import") (part "TRANSISTOR_NPNSOT23-3"))
    )
    (comp (ref "R3")
      (value "1k1")
      (footprint "eagle-import:0603")
      (fields (field (name "PARTNO") "CR0603JA0112G"))
      (libsource (lib "eagle-import") (part "RESISTOR0603"))
    )
    (comp (ref "R6")
      (value "10k")
      (footprint "eagle-import:0603")
      (fields (field (name "PARTNO") "CR0603JA0103G"))
      (libsource (lib "eagle-import") (part "RESISTOR0603"))
    )
    (comp (ref "R7")
      (value "1k1")
      (footprint "eagle-import:0603")
      (fields (field (name "PARTNO") "CR0603JA0112G"))
      (libsource (lib "eagle-import") (part "RESISTOR0603"))
    )
    (comp (ref "R21")
      (value "51k")
      (footprint "eagle-import:0603")
      (fields (field (name "PARTNO") "CR0603FA5102G "))
      (libsource (lib "eagle-import") (part "RESISTOR0603"))
    )
    (comp (ref "R24")
      (value "16k")
      (footprint "eagle-import:0603")
      (fields (field (name "PARTNO") "RC0603FR-0716KL"))
      (libsource (lib "eagle-import") (part "RESISTOR0603"))
    )
    (comp (ref "U1")
      (value "AP3211KTR-G1")
      (footprint "eagle-import:SOT23-6")
      (libsource (lib "eagle-import") (part "AP3211"))
    )
    (comp (ref "U4")
      (value "LDFPVR")
      (footprint "eagle-import:DFN6-2X2")
      (libsource (lib "eagle-import") (part "LDFPVR"))
    )
    (comp (ref "V_IN")
      (value "TPTP12R")
      (footprint "eagle-import:TP12R")
      (libsource (lib "eagle-import") (part "TPTP12R"))
    )
    (comp (ref "V_PA")
      (value "TPTP12R")
      (footprint "eagle-import:TP12R")
      (libsource (lib "eagle-import") (part "TPTP12R"))
    )
    (comp (ref "C7")
      (value "470pF")
      (footprint "eagle-import:0603")
      (fields (field (name "PARTNO") "0603B471K500CT "))
      (libsource (lib "eagle-import") (part "CAPACITOR0603"))
    )
    (comp (ref "C11")
      (value "22nF")
      (footprint "eagle-import:0603")
      (fields (field (name "PARTNO") "CL10B223KA8NNNC"))
      (libsource (lib "eagle-import") (part "CAPACITOR0603"))
    )
    (comp (ref "C29")
      (value "2.2nF")
      (footprint "eagle-import:0603")
      (fields (field (name "PARTNO") "0603N222J500CT"))
      (libsource (lib "eagle-import") (part "CAPACITOR0603"))
    )
    (comp (ref "C30")
      (value "47pF")
      (footprint "eagle-import:0603")
      (fields (field (name "PARTNO") "0603N470J500LT"))
      (libsource (lib "eagle-import") (part "CAPACITOR0603"))
    )
    (comp (ref "C36")
      (value "39pF")
      (footprint "eagle-import:0603")
      (fields (field (name "PARTNO") "0603N390J500CT"))
      (libsource (lib "eagle-import") (part "CAPACITOR0603"))
    )
    (comp (ref "C37")
      (value "47pF")
      (footprint "eagle-import:0603")
      (fields (field (name "PARTNO") "0603N470J500LT"))
      (libsource (lib "eagle-import") (part "CAPACITOR0603"))
    )
    (comp (ref "C39")
      (value "56pF")
      (footprint "eagle-import:0603")
      (fields (field (name "PARTNO") "0603N560J500CT "))
      (libsource (lib "eagle-import") (part "CAPACITOR0603"))
    )
    (comp (ref "C42")
      (value "20pF")
      (footprint "eagle-import:0603")
      (fields (field (name "PARTNO") "CL10C200JB8NNNC"))
      (libsource (lib "eagle-import") (part "CAPACITOR0603"))
    )
    (comp (ref "C44")
      (value "2.2nF")
      (footprint "eagle-import:0603")
      (fields (field (name "PARTNO") "0603N222J500CT"))
      (libsource (lib "eagle-import") (part "CAPACITOR0603"))
    )
    (comp (ref "C52")
      (value "36pF")
      (footprint "eagle-import:0603")
      (fields (field (name "PARTNO") "0603N360J500CT"))
      (libsource (lib "eagle-import") (part "CAPACITOR0603"))
    )
    (comp (ref "C53")
      (value "36pF")
      (footprint "eagle-import:0603")
      (fields (field (name "PARTNO") "0603N360J500CT"))
      (libsource (lib "eagle-import") (part "CAPACITOR0603"))
    )
    (comp (ref "L3")
      (value "36nH")
      (footprint "eagle-import:0603")
      (fields (field (name "PARTNO") "LQW18AN36NG00D"))
      (libsource (lib "eagle-import") (part "INDUCTOR0603"))
    )
    (comp (ref "L4")
      (value "2.2uH")
      (footprint "eagle-import:0805")
      (fields (field (name "PARTNO") "LQM21PN2R2MGSD"))
      (libsource (lib "eagle-import") (part "INDUCTOR0805"))
    )
    (comp (ref "L9")
      (value "18nH")
      (footprint "eagle-import:0603")
      (fields (field (name "PARTNO") "LQW18AN18NG00D"))
      (libsource (lib "eagle-import") (part "INDUCTOR0603"))
    )
    (comp (ref "L10")
      (value "22nH")
      (footprint "eagle-import:0603")
      (fields (field (name "PARTNO") "LQW18AN22NJ00D"))
      (libsource (lib "eagle-import") (part "INDUCTOR0603"))
    )
    (comp (ref "L17")
      (value "470nH")
      (footprint "eagle-import:0603")
      (fields (field (name "PARTNO") "HBLS1608-R47J "))
      (libsource (lib "eagle-import") (part "INDUCTOR0603"))
    )
    (comp (ref "L23")
      (value "39nH")
      (footprint "eagle-import:0603")
      (fields (field (name "PARTNO") "LQW18AN39NG00D"))
      (libsource (lib "eagle-import") (part "INDUCTOR0603"))
    )
    (comp (ref "R11")
      (value "2k2")
      (footprint "eagle-import:0603")
      (fields (field (name "PARTNO") "RC0603FR-072K2L"))
      (libsource (lib "eagle-import") (part "RESISTOR0603"))
    )
    (comp (ref "R12")
      (value "10k")
      (footprint "eagle-import:0603")
      (fields (field (name "PARTNO") "CR0603JA0103G"))
      (libsource (lib "eagle-import") (part "RESISTOR0603"))
    )
    (comp (ref "U7")
      (value "AFT05MS003NT1")
      (footprint "eagle-import:SOT-89")
      (libsource (lib "eagle-import") (part "AFT0SMS003N"))
    )
    (comp (ref "BOOT0")
      (value "TPTP12R")
      (footprint "eagle-import:TP12R")
      (libsource (lib "eagle-import") (part "TPTP12R"))
    )
    (comp (ref "C26")
      (value ".1uF")
      (footprint "eagle-import:0603")
      (fields (field (name "PARTNO") "0603B104K250CT"))
      (libsource (lib "eagle-import") (part "CAPACITOR0603"))
    )
    (comp (ref "C28")
      (value ".1uF")
      (footprint "eagle-import:0603")
      (fields (field (name "PARTNO") "0603B104K250CT"))
      (libsource (lib "eagle-import") (part "CAPACITOR0603"))
    )
    (comp (ref "JLINK")
      (value "M05PTH")
      (footprint "eagle-import:1X05")
      (libsource (lib "eagle-import") (part "M05PTH"))
    )
    (comp (ref "NRST")
      (value "TPTP12R")
      (footprint "eagle-import:TP12R")
      (libsource (lib "eagle-import") (part "TPTP12R"))
    )
    (comp (ref "R23")
      (value "10k")
      (footprint "eagle-import:0603")
      (fields (field (name "PARTNO") "CR0603JA0103G"))
      (libsource (lib "eagle-import") (part "RESISTOR0603"))
    )
    (comp (ref "RX")
      (value "TPTP12R")
      (footprint "eagle-import:TP12R")
      (libsource (lib "eagle-import") (part "TPTP12R"))
    )
    (comp (ref "S1")
      (value "KMR221NGLFS")
      (footprint "eagle-import:KMR221NGLFS")
      (libsource (lib "eagle-import") (part "KMR221NGLFS"))
    )
    (comp (ref "SWCLK")
      (value "TPTP12R")
      (footprint "eagle-import:TP12R")
      (libsource (lib "eagle-import") (part "TPTP12R"))
    )
    (comp (ref "SWDIO")
      (value "TPTP12R")
      (footprint "eagle-import:TP12R")
      (libsource (lib "eagle-import") (part "TPTP12R"))
    )
    (comp (ref "TX")
      (value "TPTP12R")
      (footprint "eagle-import:TP12R")
      (libsource (lib "eagle-import") (part "TPTP12R"))
    )
    (comp (ref "U13")
      (value "STM32L432KBU6")
      (footprint "eagle-import:QFN32")
      (libsource (lib "eagle-import") (part "STM32L432KXXX"))
    )
    (comp (ref "JP1")
      (value "95501-2821")
      (footprint "eagle-import:RJ45-8")
      (libsource (lib "eagle-import") (part "RJ45-8PTH"))
    )
    (comp (ref "R2")
      (value "1k1")
      (footprint "eagle-import:0603")
      (fields (field (name "PARTNO") "CR0603JA0112G"))
      (libsource (lib "eagle-import") (part "RESISTOR0603"))
    )
    (comp (ref "R13")
      (value "1k1")
      (footprint "eagle-import:0603")
      (fields (field (name "PARTNO") "CR0603JA0112G"))
      (libsource (lib "eagle-import") (part "RESISTOR0603"))
    )
    (comp (ref "R14")
      (value "100R")
      (footprint "eagle-import:0603")
      (fields (field (name "PARTNO") "RMC1/16K101FTP "))
      (libsource (lib "eagle-import") (part "RESISTOR0603"))
    )
    (comp (ref "R15")
      (value "100R")
      (footprint "eagle-import:0603")
      (fields (field (name "PARTNO") "RMC1/16K101FTP "))
      (libsource (lib "eagle-import") (part "RESISTOR0603"))
    )
    (comp (ref "R17")
      (value "100R")
      (footprint "eagle-import:0603")
      (fields (field (name "PARTNO") "RMC1/16K101FTP "))
      (libsource (lib "eagle-import") (part "RESISTOR0603"))
    )
    (comp (ref "R18")
      (value "10k")
      (footprint "eagle-import:0603")
      (fields (field (name "PARTNO") "CR0603JA0103G"))
      (libsource (lib "eagle-import") (part "RESISTOR0603"))
    )
    (comp (ref "U$1")
      (value "FIDUCIAL")
      (footprint "eagle-import:FIDUCIAL_1MM")
      (libsource (lib "eagle-import") (part "FIDUCIAL"))
    )
    (comp (ref "U$2")
      (value "FIDUCIAL")
      (footprint "eagle-import:FIDUCIAL_1MM")
      (libsource (lib "eagle-import") (part "FIDUCIAL"))
    )
    (comp (ref "U$3")
      (value "FIDUCIAL")
      (footprint "eagle-import:FIDUCIAL_1MM")
      (libsource (lib "eagle-import") (part "FIDUCIAL"))
    )
    (comp (ref "U6")
      (value "AZ23C3V6-7-F")
      (footprint "eagle-import:SOT-23")
      (libsource (lib "eagle-import") (part "AZ23C3V6-7-F"))
    )
    (comp (ref "U9")
      (value "D3V3X8U9LP3810")
      (footprint "eagle-import:U-DFN3810-9(B)")
      (libsource (lib "eagle-import") (part "D3V3X8U9LP3810"))
    )
    (comp (ref "U14")
      (value "SI1926DL-T1-E3")
      (footprint "eagle-import:SOT363")
      (fields (field (name "PARTNO") "SI1926DL-T1-E3 "))
      (libsource (lib "eagle-import") (part "DMN63D8LDW"))
    )
    (comp (ref "U17")
      (value "SI1926DL-T1-E3")
      (footprint "eagle-import:SOT363")
      (fields (field (name "PARTNO") "SI1926DL-T1-E3 "))
      (libsource (lib "eagle-import") (part "DMN63D8LDW"))
    )
  )
  (nets
    (net (code "1") (name "3.3V") (class "Default")
      (node (ref "3V3") (pin "TP") (pinfunction "TP_TP") (pintype "input"))
      (node (ref "C14") (pin "P$1") (pinfunction "1_P$1") (pintype "passive"))
      (node (ref "C15") (pin "P$1") (pinfunction "1_P$1") (pintype "passive"))
      (node (ref "C16") (pin "P$1") (pinfunction "1_P$1") (pintype "passive"))
      (node (ref "C17") (pin "P$1") (pinfunction "1_P$1") (pintype "passive"))
      (node (ref "C26") (pin "P$1") (pinfunction "1_P$1") (pintype "passive"))
      (node (ref "C28") (pin "P$1") (pinfunction "1_P$1") (pintype "passive"))
      (node (ref "C32") (pin "P$1") (pinfunction "1_P$1") (pintype "passive"))
      (node (ref "C34") (pin "P$1") (pinfunction "1_P$1") (pintype "passive"))
      (node (ref "C6") (pin "P$1") (pinfunction "1_P$1") (pintype "passive"))
      (node (ref "JLINK") (pin "5") (pinfunction "5_5") (pintype "passive"))
      (node (ref "L12") (pin "P$2") (pinfunction "2_P$2") (pintype "passive"))
      (node (ref "Q1") (pin "2") (pinfunction "S_2") (pintype "passive"))
      (node (ref "Q2") (pin "2") (pinfunction "S_2") (pintype "passive"))
      (node (ref "R1") (pin "P$2") (pinfunction "P$2_P$2") (pintype "passive"))
      (node (ref "R21") (pin "P$2") (pinfunction "P$2_P$2") (pintype "passive"))
      (node (ref "R22") (pin "P$2") (pinfunction "P$2_P$2") (pintype "passive"))
      (node (ref "U11") (pin "6") (pinfunction "VDD_1_6") (pintype "power_in"))
      (node (ref "U11") (pin "8") (pinfunction "VDD_2_8") (pintype "power_in"))
      (node (ref "U12") (pin "6") (pinfunction "VDD_1_6") (pintype "power_in"))
      (node (ref "U12") (pin "8") (pinfunction "VDD_2_8") (pintype "power_in"))
      (node (ref "U13") (pin "1") (pinfunction "VDD_1") (pintype "bidirectional"))
      (node (ref "U13") (pin "17") (pinfunction "VDD_17") (pintype "bidirectional"))
      (node (ref "U13") (pin "5") (pinfunction "VDDA_5") (pintype "bidirectional"))
      (node (ref "U15") (pin "4") (pinfunction "VCC_4") (pintype "bidirectional"))
      (node (ref "U2") (pin "P$6") (pinfunction "VBAT_P$6") (pintype "bidirectional"))
      (node (ref "U3") (pin "P$8") (pinfunction "EN_P$8") (pintype "bidirectional"))
      (node (ref "U3") (pin "P$9") (pinfunction "VCC_P$9") (pintype "bidirectional"))
    )
    (net (code "2") (name "BOOT0") (class "Default")
      (node (ref "BOOT0") (pin "TP") (pinfunction "TP_TP") (pintype "input"))
      (node (ref "R23") (pin "P$1") (pinfunction "P$1_P$1") (pintype "passive"))
      (node (ref "U13") (pin "31") (pinfunction "BOOT0_31") (pintype "bidirectional"))
    )
    (net (code "3") (name "CS1") (class "Default")
      (node (ref "U11") (pin "15") (pinfunction "NSEL_15") (pintype "input"))
      (node (ref "U13") (pin "10") (pinfunction "PA4_10") (pintype "bidirectional"))
    )
    (net (code "4") (name "CS2") (class "Default")
      (node (ref "U12") (pin "15") (pinfunction "NSEL_15") (pintype "input"))
      (node (ref "U13") (pin "6") (pinfunction "PA0_6") (pintype "bidirectional"))
    )
    (net (code "5") (name "GND") (class "Default")
      (node (ref "C1") (pin "P$2") (pinfunction "2_P$2") (pintype "passive"))
      (node (ref "C11") (pin "P$2") (pinfunction "2_P$2") (pintype "passive"))
      (node (ref "C13") (pin "P$2") (pinfunction "2_P$2") (pintype "passive"))
      (node (ref "C14") (pin "P$2") (pinfunction "2_P$2") (pintype "passive"))
      (node (ref "C15") (pin "P$2") (pinfunction "2_P$2") (pintype "passive"))
      (node (ref "C16") (pin "P$2") (pinfunction "2_P$2") (pintype "passive"))
      (node (ref "C17") (pin "P$2") (pinfunction "2_P$2") (pintype "passive"))
      (node (ref "C21") (pin "P$2") (pinfunction "2_P$2") (pintype "passive"))
      (node (ref "C23") (pin "P$2") (pinfunction "2_P$2") (pintype "passive"))
      (node (ref "C26") (pin "P$2") (pinfunction "2_P$2") (pintype "passive"))
      (node (ref "C28") (pin "P$2") (pinfunction "2_P$2") (pintype "passive"))
      (node (ref "C3") (pin "P$2") (pinfunction "2_P$2") (pintype "passive"))
      (node (ref "C30") (pin "P$2") (pinfunction "2_P$2") (pintype "passive"))
      (node (ref "C32") (pin "P$2") (pinfunction "2_P$2") (pintype "passive"))
      (node (ref "C34") (pin "P$2") (pinfunction "2_P$2") (pintype "passive"))
      (node (ref "C36") (pin "P$2") (pinfunction "2_P$2") (pintype "passive"))
      (node (ref "C37") (pin "P$2") (pinfunction "2_P$2") (pintype "passive"))
      (node (ref "C39") (pin "P$2") (pinfunction "2_P$2") (pintype "passive"))
      (node (ref "C4") (pin "P$2") (pinfunction "2_P$2") (pintype "passive"))
      (node (ref "C42") (pin "P$2") (pinfunction "2_P$2") (pintype "passive"))
      (node (ref "C43") (pin "P$2") (pinfunction "2_P$2") (pintype "passive"))
      (node (ref "C47") (pin "P$2") (pinfunction "2_P$2") (pintype "passive"))
      (node (ref "C49") (pin "P$2") (pinfunction "2_P$2") (pintype "passive"))
      (node (ref "C5") (pin "P$2") (pinfunction "2_P$2") (pintype "passive"))
      (node (ref "C52") (pin "P$2") (pinfunction "2_P$2") (pintype "passive"))
      (node (ref "C53") (pin "P$2") (pinfunction "2_P$2") (pintype "passive"))
      (node (ref "C6") (pin "P$2") (pinfunction "2_P$2") (pintype "passive"))
      (node (ref "C7") (pin "P$2") (pinfunction "2_P$2") (pintype "passive"))
      (node (ref "C8") (pin "P$2") (pinfunction "2_P$2") (pintype "passive"))
      (node (ref "D1") (pin "A") (pinfunction "A_A") (pintype "passive"))
      (node (ref "D4") (pin "A") (pinfunction "A_A") (pintype "passive"))
      (node (ref "GND1") (pin "TP") (pinfunction "TP_TP") (pintype "input"))
      (node (ref "GND2") (pin "TP") (pinfunction "TP_TP") (pintype "input"))
      (node (ref "J$1") (pin "GND@0") (pinfunction "GND_GND@0") (pintype "bidirectional"))
      (node (ref "J$1") (pin "GND@1") (pinfunction "GND_GND@1") (pintype "bidirectional"))
      (node (ref "J$1") (pin "GND@2") (pinfunction "GND_GND@2") (pintype "bidirectional"))
      (node (ref "J$1") (pin "GND@3") (pinfunction "GND_GND@3") (pintype "bidirectional"))
      (node (ref "JLINK") (pin "1") (pinfunction "1_1") (pintype "passive"))
      (node (ref "JP1") (pin "8") (pinfunction "8_8") (pintype "bidirectional"))
      (node (ref "L14") (pin "P$1") (pinfunction "1_P$1") (pintype "passive"))
      (node (ref "R12") (pin "P$1") (pinfunction "P$1_P$1") (pintype "passive"))
      (node (ref "R18") (pin "P$1") (pinfunction "P$1_P$1") (pintype "passive"))
      (node (ref "R23") (pin "P$2") (pinfunction "P$2_P$2") (pintype "passive"))
      (node (ref "R24") (pin "P$1") (pinfunction "P$1_P$1") (pintype "passive"))
      (node (ref "R3") (pin "P$1") (pinfunction "P$1_P$1") (pintype "passive"))
      (node (ref "R5") (pin "P$1") (pinfunction "P$1_P$1") (pintype "passive"))
      (node (ref "S1") (pin "P$2") (pinfunction "S2_P$2") (pintype "bidirectional"))
      (node (ref "SWDIO1") (pin "TP") (pinfunction "TP_TP") (pintype "input"))
      (node (ref "SWDIO2") (pin "TP") (pinfunction "TP_TP") (pintype "input"))
      (node (ref "SWDIO3") (pin "TP") (pinfunction "TP_TP") (pintype "input"))
      (node (ref "SWDIO4") (pin "TP") (pinfunction "TP_TP") (pintype "input"))
      (node (ref "SWDIO5") (pin "TP") (pinfunction "TP_TP") (pintype "input"))
      (node (ref "SWDIO6") (pin "TP") (pinfunction "TP_TP") (pintype "input"))
      (node (ref "U1") (pin "2") (pinfunction "GND_2") (pintype "bidirectional"))
      (node (ref "U11") (pin "18") (pinfunction "GNDX_18") (pintype "bidirectional"))
      (node (ref "U11") (pin "3") (pinfunction "RXN_3") (pintype "input"))
      (node (ref "U11") (pin "5") (pinfunction "NC_5") (pintype "bidirectional"))
      (node (ref "U11") (pin "EXP") (pinfunction "PAD_EXP") (pintype "bidirectional"))
      (node (ref "U12") (pin "18") (pinfunction "GNDX_18") (pintype "bidirectional"))
      (node (ref "U12") (pin "3") (pinfunction "RXN_3") (pintype "input"))
      (node (ref "U12") (pin "5") (pinfunction "NC_5") (pintype "bidirectional"))
      (node (ref "U12") (pin "EXP") (pinfunction "PAD_EXP") (pintype "bidirectional"))
      (node (ref "U13") (pin "16") (pinfunction "VSS_16") (pintype "bidirectional"))
      (node (ref "U13") (pin "32") (pinfunction "VSS_32") (pintype "bidirectional"))
      (node (ref "U13") (pin "EXP") (pinfunction "PAD_EXP") (pintype "bidirectional"))
      (node (ref "U14") (pin "1") (pinfunction "S_1") (pintype "bidirectional"))
      (node (ref "U14") (pin "4") (pinfunction "S_4") (pintype "bidirectional"))
      (node (ref "U15") (pin "2") (pinfunction "GND_2") (pintype "bidirectional"))
      (node (ref "U15") (pin "5") (pinfunction "WP_5") (pintype "bidirectional"))
      (node (ref "U17") (pin "1") (pinfunction "S_1") (pintype "bidirectional"))
      (node (ref "U17") (pin "4") (pinfunction "S_4") (pintype "bidirectional"))
      (node (ref "U2") (pin "P$1") (pinfunction "GND_P$1") (pintype "bidirectional"))
      (node (ref "U2") (pin "P$10") (pinfunction "GND_P$10") (pintype "bidirectional"))
      (node (ref "U2") (pin "P$12") (pinfunction "GND_P$12") (pintype "bidirectional"))
      (node (ref "U3") (pin "P$1") (pinfunction "GND_P$1") (pintype "bidirectional"))
      (node (ref "U3") (pin "P$10") (pinfunction "GND_P$10") (pintype "bidirectional"))
      (node (ref "U3") (pin "P$12") (pinfunction "GND_P$12") (pintype "bidirectional"))
      (node (ref "U3") (pin "P$13") (pinfunction "GND_P$13") (pintype "bidirectional"))
      (node (ref "U3") (pin "P$3") (pinfunction "GND_P$3") (pintype "bidirectional"))
      (node (ref "U3") (pin "P$4") (pinfunction "GND_P$4") (pintype "bidirectional"))
      (node (ref "U3") (pin "P$6") (pinfunction "GND_P$6") (pintype "bidirectional"))
      (node (ref "U4") (pin "P$4") (pinfunction "GND_P$4") (pintype "bidirectional"))
      (node (ref "U4") (pin "P$7") (pinfunction "GND_P$7") (pintype "bidirectional"))
      (node (ref "U5") (pin "2") (pinfunction "GND_2") (pintype "bidirectional"))
      (node (ref "U5") (pin "4") (pinfunction "GND_4") (pintype "bidirectional"))
      (node (ref "U5") (pin "5") (pinfunction "GND_5") (pintype "bidirectional"))
      (node (ref "U6") (pin "3") (pinfunction "P$3_3") (pintype "bidirectional"))
      (node (ref "U7") (pin "2") (pinfunction "S_2") (pintype "passive"))
      (node (ref "U7") (pin "2@1") (pinfunction "PAD_2@1") (pintype "bidirectional"))
      (node (ref "U9") (pin "P$3") (pinfunction "GND_P$3") (pintype "bidirectional"))
      (node (ref "X1") (pin "2") (pinfunction "G2_2") (pintype "power_in"))
      (node (ref "X1") (pin "4") (pinfunction "G1_4") (pintype "power_in"))
      (node (ref "X2") (pin "2") (pinfunction "G2_2") (pintype "power_in"))
      (node (ref "X2") (pin "4") (pinfunction "G1_4") (pintype "power_in"))
      (node (ref "Z2") (pin "P$1") (pinfunction "P$1_P$1") (pintype "passive"))
      (node (ref "Z3") (pin "P$1") (pinfunction "P$1_P$1") (pintype "passive"))
    )
    (net (code "6") (name "GPS_1PPS") (class "Default")
      (node (ref "U13") (pin "8") (pinfunction "PA2_8") (pintype "bidirectional"))
      (node (ref "U2") (pin "P$4") (pinfunction "1PPS_P$4") (pintype "bidirectional"))
    )
    (net (code "7") (name "GPS_EN") (class "Default")
      (node (ref "Q2") (pin "1") (pinfunction "G_1") (pintype "passive"))
      (node (ref "R1") (pin "P$1") (pinfunction "P$1_P$1") (pintype "passive"))
      (node (ref "U13") (pin "2") (pinfunction "OSC_IN/PC14_2") (pintype "bidirectional"))
    )
    (net (code "8") (name "GPS_STATUS") (class "Default")
      (node (ref "U13") (pin "21") (pinfunction "PA11_21") (pintype "bidirectional"))
      (node (ref "U14") (pin "5") (pinfunction "G_5") (pintype "bidirectional"))
    )
    (net (code "9") (name "GPS_UART_TX") (class "Default")
      (node (ref "U13") (pin "9") (pinfunction "PA3_9") (pintype "bidirectional"))
      (node (ref "U2") (pin "P$2") (pinfunction "TX_P$2") (pintype "bidirectional"))
    )
    (net (code "10") (name "HOST_GPS_STATUS") (class "Default")
      (node (ref "JP1") (pin "4") (pinfunction "4_4") (pintype "bidirectional"))
      (node (ref "R14") (pin "P$2") (pinfunction "P$2_P$2") (pintype "passive"))
      (node (ref "U9") (pin "P$2") (pinfunction "C2_P$2") (pintype "bidirectional"))
    )
    (net (code "11") (name "HOST_RX_STATUS") (class "Default")
      (node (ref "JP1") (pin "6") (pinfunction "6_6") (pintype "bidirectional"))
      (node (ref "R15") (pin "P$2") (pinfunction "P$2_P$2") (pintype "passive"))
      (node (ref "U9") (pin "P$7") (pinfunction "C6_P$7") (pintype "bidirectional"))
    )
    (net (code "12") (name "HOST_TX_OFF") (class "Default")
      (node (ref "JP1") (pin "2") (pinfunction "2_2") (pintype "bidirectional"))
      (node (ref "R18") (pin "P$2") (pinfunction "P$2_P$2") (pintype "passive"))
      (node (ref "U17") (pin "2") (pinfunction "G_2") (pintype "bidirectional"))
      (node (ref "U9") (pin "P$1") (pinfunction "C1_P$1") (pintype "bidirectional"))
    )
    (net (code "13") (name "HOST_TX_STATUS") (class "Default")
      (node (ref "JP1") (pin "7") (pinfunction "7_7") (pintype "bidirectional"))
      (node (ref "R17") (pin "P$2") (pinfunction "P$2_P$2") (pintype "passive"))
      (node (ref "U9") (pin "P$6") (pinfunction "C5_P$6") (pintype "bidirectional"))
    )
    (net (code "14") (name "HOST_UART_RX") (class "Default")
      (node (ref "JP1") (pin "5") (pinfunction "5_5") (pintype "bidirectional"))
      (node (ref "R13") (pin "P$2") (pinfunction "P$2_P$2") (pintype "passive"))
      (node (ref "U9") (pin "P$8") (pinfunction "C7_P$8") (pintype "bidirectional"))
    )
    (net (code "15") (name "HOST_UART_TX") (class "Default")
      (node (ref "JP1") (pin "3") (pinfunction "3_3") (pintype "bidirectional"))
      (node (ref "R2") (pin "P$2") (pinfunction "P$2_P$2") (pintype "passive"))
      (node (ref "U9") (pin "P$9") (pinfunction "C8_P$9") (pintype "bidirectional"))
    )
    (net (code "16") (name "I2C_SCL") (class "Default")
      (node (ref "U13") (pin "29") (pinfunction "PB6_29") (pintype "bidirectional"))
      (node (ref "U15") (pin "1") (pinfunction "SCL_1") (pintype "bidirectional"))
    )
    (net (code "17") (name "I2C_SDA") (class "Default")
      (node (ref "U13") (pin "30") (pinfunction "PB7_30") (pintype "bidirectional"))
      (node (ref "U15") (pin "3") (pinfunction "SDA_3") (pintype "bidirectional"))
    )
    (net (code "18") (name "MCU_TX_OFF") (class "Default")
      (node (ref "U13") (pin "22") (pinfunction "PA12_22") (pintype "bidirectional"))
      (node (ref "U17") (pin "6") (pinfunction "D_6") (pintype "bidirectional"))
    )
    (net (code "19") (name "MCU_UART_RX") (class "Default")
      (node (ref "R2") (pin "P$1") (pinfunction "P$1_P$1") (pintype "passive"))
      (node (ref "RX") (pin "TP") (pinfunction "TP_TP") (pintype "input"))
      (node (ref "U13") (pin "20") (pinfunction "PA10_20") (pintype "bidirectional"))
      (node (ref "U6") (pin "1") (pinfunction "P$1_1") (pintype "bidirectional"))
    )
    (net (code "20") (name "MCU_UART_TX") (class "Default")
      (node (ref "R13") (pin "P$1") (pinfunction "P$1_P$1") (pintype "passive"))
      (node (ref "TX") (pin "TP") (pinfunction "TP_TP") (pintype "input"))
      (node (ref "U13") (pin "19") (pinfunction "PA9_19") (pintype "bidirectional"))
      (node (ref "U6") (pin "2") (pinfunction "P$2_2") (pintype "bidirectional"))
    )
    (net (code "21") (name "MISO") (class "Default")
      (node (ref "U11") (pin "13") (pinfunction "SDO_13") (pintype "output"))
      (node (ref "U12") (pin "13") (pinfunction "SDO_13") (pintype "output"))
      (node (ref "U13") (pin "12") (pinfunction "PA6_12") (pintype "bidirectional"))
    )
    (net (code "22") (name "MOSI") (class "Default")
      (node (ref "U11") (pin "14") (pinfunction "SDI_14") (pintype "input"))
      (node (ref "U12") (pin "14") (pinfunction "SDI_14") (pintype "input"))
      (node (ref "U13") (pin "13") (pinfunction "PA7_13") (pintype "bidirectional"))
    )
    (net (code "23") (name "NRST") (class "Default")
      (node (ref "JLINK") (pin "2") (pinfunction "2_2") (pintype "passive"))
      (node (ref "NRST") (pin "TP") (pinfunction "TP_TP") (pintype "input"))
      (node (ref "S1") (pin "P$1") (pinfunction "S1_P$1") (pintype "bidirectional"))
      (node (ref "U13") (pin "4") (pinfunction "NRST_4") (pintype "bidirectional"))
    )
    (net (code "24") (name "Net-(C1-1)") (class "Default")
      (node (ref "C1") (pin "P$1") (pinfunction "1_P$1") (pintype "passive"))
      (node (ref "C43") (pin "P$1") (pinfunction "1_P$1") (pintype "passive"))
      (node (ref "L2") (pin "P$2") (pinfunction "2_P$2") (pintype "passive"))
      (node (ref "U1") (pin "4") (pinfunction "EN_4") (pintype "bidirectional"))
      (node (ref "U1") (pin "5") (pinfunction "IN_5") (pintype "bidirectional"))
    )
    (net (code "25") (name "Net-(C2-1)") (class "Default")
      (node (ref "C2") (pin "P$1") (pinfunction "1_P$1") (pintype "passive"))
      (node (ref "U1") (pin "1") (pinfunction "BS_1") (pintype "bidirectional"))
    )
    (net (code "26") (name "Net-(C2-2)") (class "Default")
      (node (ref "C2") (pin "P$2") (pinfunction "2_P$2") (pintype "passive"))
      (node (ref "D4") (pin "C") (pinfunction "C_C") (pintype "passive"))
      (node (ref "L12") (pin "P$1") (pinfunction "1_P$1") (pintype "passive"))
      (node (ref "U1") (pin "6") (pinfunction "SW_6") (pintype "bidirectional"))
    )
    (net (code "27") (name "Net-(C3-1)") (class "Default")
      (node (ref "C3") (pin "P$1") (pinfunction "1_P$1") (pintype "passive"))
      (node (ref "C5") (pin "P$1") (pinfunction "1_P$1") (pintype "passive"))
      (node (ref "Q2") (pin "3") (pinfunction "D_3") (pintype "passive"))
      (node (ref "U2") (pin "P$8") (pinfunction "VCC_P$8") (pintype "bidirectional"))
    )
    (net (code "28") (name "Net-(C9-1)") (class "Default")
      (node (ref "C9") (pin "P$1") (pinfunction "1_P$1") (pintype "passive"))
      (node (ref "L8") (pin "P$2") (pinfunction "2_P$2") (pintype "passive"))
    )
    (net (code "29") (name "Net-(C10-1)") (class "Default")
      (node (ref "C10") (pin "P$1") (pinfunction "1_P$1") (pintype "passive"))
      (node (ref "C8") (pin "P$1") (pinfunction "1_P$1") (pintype "passive"))
      (node (ref "C9") (pin "P$2") (pinfunction "2_P$2") (pintype "passive"))
      (node (ref "L14") (pin "P$2") (pinfunction "2_P$2") (pintype "passive"))
    )
    (net (code "30") (name "Net-(C10-2)") (class "Default")
      (node (ref "C10") (pin "P$2") (pinfunction "2_P$2") (pintype "passive"))
      (node (ref "L13") (pin "P$1") (pinfunction "1_P$1") (pintype "passive"))
    )
    (net (code "31") (name "Net-(C12-1)") (class "Default")
      (node (ref "C12") (pin "P$1") (pinfunction "1_P$1") (pintype "passive"))
      (node (ref "L13") (pin "P$2") (pinfunction "2_P$2") (pintype "passive"))
    )
    (net (code "32") (name "Net-(C12-2)") (class "Default")
      (node (ref "C12") (pin "P$2") (pinfunction "2_P$2") (pintype "passive"))
      (node (ref "U5") (pin "6") (pinfunction "IN_6") (pintype "bidirectional"))
    )
    (net (code "33") (name "Net-(C13-1)") (class "Default")
      (node (ref "C13") (pin "P$1") (pinfunction "1_P$1") (pintype "passive"))
      (node (ref "R10") (pin "P$2") (pinfunction "P$2_P$2") (pintype "passive"))
      (node (ref "U5") (pin "1") (pinfunction "VCC_1") (pintype "bidirectional"))
    )
    (net (code "34") (name "Net-(C18-1)") (class "Default")
      (node (ref "C18") (pin "P$1") (pinfunction "1_P$1") (pintype "passive"))
      (node (ref "U5") (pin "3") (pinfunction "OUT_3") (pintype "bidirectional"))
    )
    (net (code "35") (name "Net-(C21-1)") (class "Default")
      (node (ref "C21") (pin "P$1") (pinfunction "1_P$1") (pintype "passive"))
      (node (ref "L5") (pin "P$1") (pinfunction "1_P$1") (pintype "passive"))
      (node (ref "R22") (pin "P$1") (pinfunction "P$1_P$1") (pintype "passive"))
    )
    (net (code "36") (name "Net-(C22-1)") (class "Default")
      (node (ref "C22") (pin "P$1") (pinfunction "1_P$1") (pintype "passive"))
      (node (ref "L5") (pin "P$2") (pinfunction "2_P$2") (pintype "passive"))
      (node (ref "U11") (pin "4") (pinfunction "TX_4") (pintype "output"))
    )
    (net (code "37") (name "Net-(C22-2)") (class "Default")
      (node (ref "C22") (pin "P$2") (pinfunction "2_P$2") (pintype "passive"))
      (node (ref "L1") (pin "P$1") (pinfunction "1_P$1") (pintype "passive"))
    )
    (net (code "38") (name "Net-(C23-1)") (class "Default")
      (node (ref "C23") (pin "P$1") (pinfunction "1_P$1") (pintype "passive"))
      (node (ref "L1") (pin "P$2") (pinfunction "2_P$2") (pintype "passive"))
      (node (ref "L6") (pin "P$1") (pinfunction "1_P$1") (pintype "passive"))
    )
    (net (code "39") (name "Net-(C29-2)") (class "Default")
      (node (ref "C29") (pin "P$2") (pinfunction "2_P$2") (pintype "passive"))
      (node (ref "C30") (pin "P$1") (pinfunction "1_P$1") (pintype "passive"))
      (node (ref "L3") (pin "P$1") (pinfunction "1_P$1") (pintype "passive"))
    )
    (net (code "40") (name "Net-(C36-1)") (class "Default")
      (node (ref "C36") (pin "P$1") (pinfunction "1_P$1") (pintype "passive"))
      (node (ref "L10") (pin "P$1") (pinfunction "1_P$1") (pintype "passive"))
      (node (ref "L9") (pin "P$2") (pinfunction "2_P$2") (pintype "passive"))
    )
    (net (code "41") (name "Net-(C37-1)") (class "Default")
      (node (ref "C37") (pin "P$1") (pinfunction "1_P$1") (pintype "passive"))
      (node (ref "C39") (pin "P$1") (pinfunction "1_P$1") (pintype "passive"))
      (node (ref "L4") (pin "P$2") (pinfunction "2_P$2") (pintype "passive"))
      (node (ref "L9") (pin "P$1") (pinfunction "1_P$1") (pintype "passive"))
      (node (ref "U7") (pin "3") (pinfunction "D_3") (pintype "passive"))
    )
    (net (code "42") (name "Net-(C42-1)") (class "Default")
      (node (ref "C42") (pin "P$1") (pinfunction "1_P$1") (pintype "passive"))
      (node (ref "C52") (pin "P$1") (pinfunction "1_P$1") (pintype "passive"))
      (node (ref "L10") (pin "P$2") (pinfunction "2_P$2") (pintype "passive"))
      (node (ref "L23") (pin "P$1") (pinfunction "1_P$1") (pintype "passive"))
    )
    (net (code "43") (name "Net-(C44-1)") (class "Default")
      (node (ref "C44") (pin "P$1") (pinfunction "1_P$1") (pintype "passive"))
      (node (ref "C53") (pin "P$1") (pinfunction "1_P$1") (pintype "passive"))
      (node (ref "L23") (pin "P$2") (pinfunction "2_P$2") (pintype "passive"))
    )
    (net (code "44") (name "Net-(J$1-SIGNAL)") (class "Default")
      (node (ref "J$1") (pin "SIG") (pinfunction "SIGNAL_SIG") (pintype "bidirectional"))
      (node (ref "RF") (pin "TP") (pinfunction "TP_TP") (pintype "input"))
      (node (ref "U3") (pin "P$2") (pinfunction "RF1_P$2") (pintype "bidirectional"))
    )
    (net (code "45") (name "Net-(L17-1)") (class "Default")
      (node (ref "L17") (pin "P$1") (pinfunction "1_P$1") (pintype "passive"))
      (node (ref "L3") (pin "P$2") (pinfunction "2_P$2") (pintype "passive"))
      (node (ref "U7") (pin "1") (pinfunction "G_1") (pintype "passive"))
    )
    (net (code "46") (name "Net-(Q3-B)") (class "Default")
      (node (ref "D1") (pin "C") (pinfunction "C_C") (pintype "passive"))
      (node (ref "Q3") (pin "1") (pinfunction "B_1") (pintype "passive"))
      (node (ref "R7") (pin "P$1") (pinfunction "P$1_P$1") (pintype "passive"))
    )
    (net (code "47") (name "Net-(U1-FB)") (class "Default")
      (node (ref "R21") (pin "P$1") (pinfunction "P$1_P$1") (pintype "passive"))
      (node (ref "R24") (pin "P$2") (pinfunction "P$2_P$2") (pintype "passive"))
      (node (ref "U1") (pin "3") (pinfunction "FB_3") (pintype "bidirectional"))
    )
    (net (code "48") (name "Net-(U2-RFIN)") (class "Default")
      (node (ref "U2") (pin "P$11") (pinfunction "RFIN_P$11") (pintype "bidirectional"))
      (node (ref "Z1") (pin "P$2") (pinfunction "P$2_P$2") (pintype "passive"))
      (node (ref "Z3") (pin "P$2") (pinfunction "P$2_P$2") (pintype "passive"))
    )
    (net (code "49") (name "Net-(U4-ADJ)") (class "Default")
      (node (ref "R3") (pin "P$2") (pinfunction "P$2_P$2") (pintype "passive"))
      (node (ref "R6") (pin "P$1") (pinfunction "P$1_P$1") (pintype "passive"))
      (node (ref "U4") (pin "P$2") (pinfunction "ADJ_P$2") (pintype "bidirectional"))
    )
    (net (code "50") (name "Net-(U10-RF)") (class "Default")
      (node (ref "U10") (pin "P$1") (pinfunction "RF_P$1") (pintype "bidirectional"))
      (node (ref "Z1") (pin "P$1") (pinfunction "P$1_P$1") (pintype "passive"))
      (node (ref "Z2") (pin "P$2") (pinfunction "P$2_P$2") (pintype "passive"))
    )
    (net (code "51") (name "Net-(U11-XIN)") (class "Default")
      (node (ref "U11") (pin "17") (pinfunction "XIN_17") (pintype "input"))
      (node (ref "X1") (pin "3") (pinfunction "X2_3") (pintype "bidirectional"))
    )
    (net (code "52") (name "Net-(U11-XOUT)") (class "Default")
      (node (ref "U11") (pin "16") (pinfunction "XOUT_16") (pintype "bidirectional"))
      (node (ref "X1") (pin "1") (pinfunction "X1_1") (pintype "bidirectional"))
    )
    (net (code "53") (name "Net-(U12-XIN)") (class "Default")
      (node (ref "U12") (pin "17") (pinfunction "XIN_17") (pintype "input"))
      (node (ref "X2") (pin "3") (pinfunction "X2_3") (pintype "bidirectional"))
    )
    (net (code "54") (name "Net-(U12-XOUT)") (class "Default")
      (node (ref "U12") (pin "16") (pinfunction "XOUT_16") (pintype "bidirectional"))
      (node (ref "X2") (pin "1") (pinfunction "X1_1") (pintype "bidirectional"))
    )
    (net (code "55") (name "Net-(U14A-D)") (class "Default")
      (node (ref "R14") (pin "P$1") (pinfunction "P$1_P$1") (pintype "passive"))
      (node (ref "U14") (pin "3") (pinfunction "D_3") (pintype "bidirectional"))
    )
    (net (code "56") (name "Net-(U14B-D)") (class "Default")
      (node (ref "R15") (pin "P$1") (pinfunction "P$1_P$1") (pintype "passive"))
      (node (ref "U14") (pin "6") (pinfunction "D_6") (pintype "bidirectional"))
    )
    (net (code "57") (name "Net-(U17A-D)") (class "Default")
      (node (ref "R17") (pin "P$1") (pinfunction "P$1_P$1") (pintype "passive"))
      (node (ref "U17") (pin "3") (pinfunction "D_3") (pintype "bidirectional"))
    )
    (net (code "58") (name "PA_GATE_BIAS") (class "Default")
      (node (ref "C11") (pin "P$1") (pinfunction "1_P$1") (pintype "passive"))
      (node (ref "L17") (pin "P$2") (pinfunction "2_P$2") (pintype "passive"))
      (node (ref "R11") (pin "P$1") (pinfunction "P$1_P$1") (pintype "passive"))
      (node (ref "R12") (pin "P$2") (pinfunction "P$2_P$2") (pintype "passive"))
    )
    (net (code "59") (name "PA_IN") (class "Default")
      (node (ref "C29") (pin "P$1") (pinfunction "1_P$1") (pintype "passive"))
      (node (ref "L6") (pin "P$2") (pinfunction "2_P$2") (pintype "passive"))
    )
    (net (code "60") (name "PA_OUT") (class "Default")
      (node (ref "C44") (pin "P$2") (pinfunction "2_P$2") (pintype "passive"))
      (node (ref "U3") (pin "P$5") (pinfunction "RF3_P$5") (pintype "bidirectional"))
    )
    (net (code "61") (name "RFSW_CTRL") (class "Default")
      (node (ref "Q1") (pin "1") (pinfunction "G_1") (pintype "passive"))
      (node (ref "U11") (pin "20") (pinfunction "GPIO3_20") (pintype "bidirectional"))
    )
    (net (code "62") (name "RF_IN") (class "Default")
      (node (ref "L8") (pin "P$1") (pinfunction "1_P$1") (pintype "passive"))
      (node (ref "U3") (pin "P$11") (pinfunction "RF2_P$11") (pintype "bidirectional"))
    )
    (net (code "63") (name "RX_EN") (class "Default")
      (node (ref "R4") (pin "P$2") (pinfunction "P$2_P$2") (pintype "passive"))
      (node (ref "R5") (pin "P$2") (pinfunction "P$2_P$2") (pintype "passive"))
      (node (ref "U3") (pin "P$7") (pinfunction "CTRL_P$7") (pintype "bidirectional"))
    )
    (net (code "64") (name "RX_IC_CLK") (class "Default")
      (node (ref "U12") (pin "20") (pinfunction "GPIO3_20") (pintype "bidirectional"))
      (node (ref "U13") (pin "26") (pinfunction "PB3_26") (pintype "bidirectional"))
    )
    (net (code "65") (name "RX_IC_DATA") (class "Default")
      (node (ref "U12") (pin "10") (pinfunction "GPIO1_10") (pintype "bidirectional"))
      (node (ref "U13") (pin "27") (pinfunction "PB4_27") (pintype "bidirectional"))
    )
    (net (code "66") (name "RX_IN") (class "Default")
      (node (ref "C18") (pin "P$2") (pinfunction "2_P$2") (pintype "passive"))
      (node (ref "U11") (pin "2") (pinfunction "RXP_2") (pintype "input"))
      (node (ref "U12") (pin "2") (pinfunction "RXP_2") (pintype "input"))
    )
    (net (code "67") (name "RX_STATUS") (class "Default")
      (node (ref "U13") (pin "7") (pinfunction "PA1_7") (pintype "bidirectional"))
      (node (ref "U14") (pin "2") (pinfunction "G_2") (pintype "bidirectional"))
    )
    (net (code "68") (name "SCK") (class "Default")
      (node (ref "U11") (pin "12") (pinfunction "SCLK_12") (pintype "input"))
      (node (ref "U12") (pin "12") (pinfunction "SCLK_12") (pintype "input"))
      (node (ref "U13") (pin "11") (pinfunction "PA5_11") (pintype "bidirectional"))
    )
    (net (code "69") (name "SDN1") (class "Default")
      (node (ref "U11") (pin "1") (pinfunction "SDN_1") (pintype "input"))
      (node (ref "U13") (pin "14") (pinfunction "PB0_14") (pintype "bidirectional"))
    )
    (net (code "70") (name "SDN2") (class "Default")
      (node (ref "U12") (pin "1") (pinfunction "SDN_1") (pintype "input"))
      (node (ref "U13") (pin "25") (pinfunction "PA15_25") (pintype "bidirectional"))
    )
    (net (code "71") (name "SWCLK") (class "Default")
      (node (ref "JLINK") (pin "3") (pinfunction "3_3") (pintype "passive"))
      (node (ref "SWCLK") (pin "TP") (pinfunction "TP_TP") (pintype "input"))
      (node (ref "U13") (pin "24") (pinfunction "PA14_24") (pintype "bidirectional"))
    )
    (net (code "72") (name "SWDIO") (class "Default")
      (node (ref "JLINK") (pin "4") (pinfunction "4_4") (pintype "passive"))
      (node (ref "SWDIO") (pin "TP") (pinfunction "TP_TP") (pintype "input"))
      (node (ref "U13") (pin "23") (pinfunction "PA13_23") (pintype "bidirectional"))
    )
    (net (code "73") (name "TRX_IC_CLOCK") (class "Default")
      (node (ref "U11") (pin "19") (pinfunction "GPIO2_19") (pintype "bidirectional"))
      (node (ref "U13") (pin "3") (pinfunction "OSC_OUT/PC15_3") (pintype "bidirectional"))
    )
    (net (code "74") (name "TRX_IC_DATA") (class "Default")
      (node (ref "U11") (pin "10") (pinfunction "GPIO1_10") (pintype "bidirectional"))
      (node (ref "U13") (pin "15") (pinfunction "PB1_15") (pintype "bidirectional"))
    )
    (net (code "75") (name "TX_STATUS") (class "Default")
      (node (ref "U13") (pin "28") (pinfunction "PB5_28") (pintype "bidirectional"))
      (node (ref "U17") (pin "5") (pinfunction "G_5") (pintype "bidirectional"))
    )
    (net (code "76") (name "V_IN") (class "Default")
      (node (ref "C4") (pin "P$1") (pinfunction "1_P$1") (pintype "passive"))
      (node (ref "C47") (pin "P$1") (pinfunction "1_P$1") (pintype "passive"))
      (node (ref "JP1") (pin "1") (pinfunction "1_1") (pintype "bidirectional"))
      (node (ref "L2") (pin "P$1") (pinfunction "1_P$1") (pintype "passive"))
      (node (ref "Q3") (pin "3") (pinfunction "C_3") (pintype "passive"))
      (node (ref "R7") (pin "P$2") (pinfunction "P$2_P$2") (pintype "passive"))
      (node (ref "U4") (pin "P$5") (pinfunction "EN_P$5") (pintype "bidirectional"))
      (node (ref "U4") (pin "P$6") (pinfunction "VIN_P$6") (pintype "bidirectional"))
      (node (ref "V_IN") (pin "TP") (pinfunction "TP_TP") (pintype "input"))
    )
    (net (code "77") (name "V_LNA") (class "Default")
      (node (ref "Q1") (pin "3") (pinfunction "D_3") (pintype "passive"))
      (node (ref "R10") (pin "P$1") (pinfunction "P$1_P$1") (pintype "passive"))
      (node (ref "R4") (pin "P$1") (pinfunction "P$1_P$1") (pintype "passive"))
      (node (ref "V_LNA") (pin "TP") (pinfunction "TP_TP") (pintype "input"))
    )
    (net (code "78") (name "V_PA") (class "Default")
      (node (ref "C49") (pin "P$1") (pinfunction "1_P$1") (pintype "passive"))
      (node (ref "C7") (pin "P$1") (pinfunction "1_P$1") (pintype "passive"))
      (node (ref "L4") (pin "P$1") (pinfunction "1_P$1") (pintype "passive"))
      (node (ref "Q3") (pin "2") (pinfunction "E_2") (pintype "passive"))
      (node (ref "R6") (pin "P$2") (pinfunction "P$2_P$2") (pintype "passive"))
      (node (ref "U4") (pin "P$1") (pinfunction "VOUT_P$1") (pintype "bidirectional"))
      (node (ref "V_PA") (pin "TP") (pinfunction "TP_TP") (pintype "input"))
    )
    (net (code "79") (name "V_PA_BIAS") (class "Default")
      (node (ref "R11") (pin "P$2") (pinfunction "P$2_P$2") (pintype "passive"))
      (node (ref "U13") (pin "18") (pinfunction "PA8_18") (pintype "bidirectional"))
    )
    (net (code "80") (name "unconnected-(S1-S1-PadP$4)") (class "Default")
      (node (ref "S1") (pin "P$4") (pinfunction "S1_P$4") (pintype "bidirectional"))
    )
    (net (code "81") (name "unconnected-(S1-S2-PadP$3)") (class "Default")
      (node (ref "S1") (pin "P$3") (pinfunction "S2_P$3") (pintype "bidirectional"))
    )
    (net (code "82") (name "unconnected-(U2-RX-PadP$3)") (class "Default")
      (node (ref "U2") (pin "P$3") (pinfunction "RX_P$3") (pintype "bidirectional"))
    )
    (net (code "83") (name "unconnected-(U2-VIO-PadP$7)") (class "Default")
      (node (ref "U2") (pin "P$7") (pinfunction "VIO_P$7") (pintype "bidirectional"))
    )
    (net (code "84") (name "unconnected-(U4-PG-PadP$3)") (class "Default")
      (node (ref "U4") (pin "P$3") (pinfunction "PG_P$3") (pintype "bidirectional"))
    )
    (net (code "85") (name "unconnected-(U9-C3-PadP$4)") (class "Default")
      (node (ref "U9") (pin "P$4") (pinfunction "C3_P$4") (pintype "bidirectional"))
    )
    (net (code "86") (name "unconnected-(U9-C4-PadP$5)") (class "Default")
      (node (ref "U9") (pin "P$5") (pinfunction "C4_P$5") (pintype "bidirectional"))
    )
    (net (code "87") (name "unconnected-(U10-PAD-PadP$2)") (class "Default")
      (node (ref "U10") (pin "P$2") (pinfunction "PAD_P$2") (pintype "no_connect"))
    )
    (net (code "88") (name "unconnected-(U11-GPIO0-Pad9)") (class "Default")
      (node (ref "U11") (pin "9") (pinfunction "GPIO0_9") (pintype "bidirectional"))
    )
    (net (code "89") (name "unconnected-(U11-NIRQ-Pad11)") (class "Default")
      (node (ref "U11") (pin "11") (pinfunction "NIRQ_11") (pintype "bidirectional"))
    )
    (net (code "90") (name "unconnected-(U11-TXRAMP-Pad7)") (class "Default")
      (node (ref "U11") (pin "7") (pinfunction "TXRAMP_7") (pintype "bidirectional"))
    )
    (net (code "91") (name "unconnected-(U12-GPIO0-Pad9)") (class "Default")
      (node (ref "U12") (pin "9") (pinfunction "GPIO0_9") (pintype "bidirectional"))
    )
    (net (code "92") (name "unconnected-(U12-GPIO2-Pad19)") (class "Default")
      (node (ref "U12") (pin "19") (pinfunction "GPIO2_19") (pintype "bidirectional"))
    )
    (net (code "93") (name "unconnected-(U12-NIRQ-Pad11)") (class "Default")
      (node (ref "U12") (pin "11") (pinfunction "NIRQ_11") (pintype "bidirectional"))
    )
    (net (code "94") (name "unconnected-(U12-TX-Pad4)") (class "Default")
      (node (ref "U12") (pin "4") (pinfunction "TX_4") (pintype "output"))
    )
    (net (code "95") (name "unconnected-(U12-TXRAMP-Pad7)") (class "Default")
      (node (ref "U12") (pin "7") (pinfunction "TXRAMP_7") (pintype "bidirectional"))
    )
  )
)
